# 2020-09-27_06-15-33.net
KiCad netlist of a schematic drawn in EasyEDA
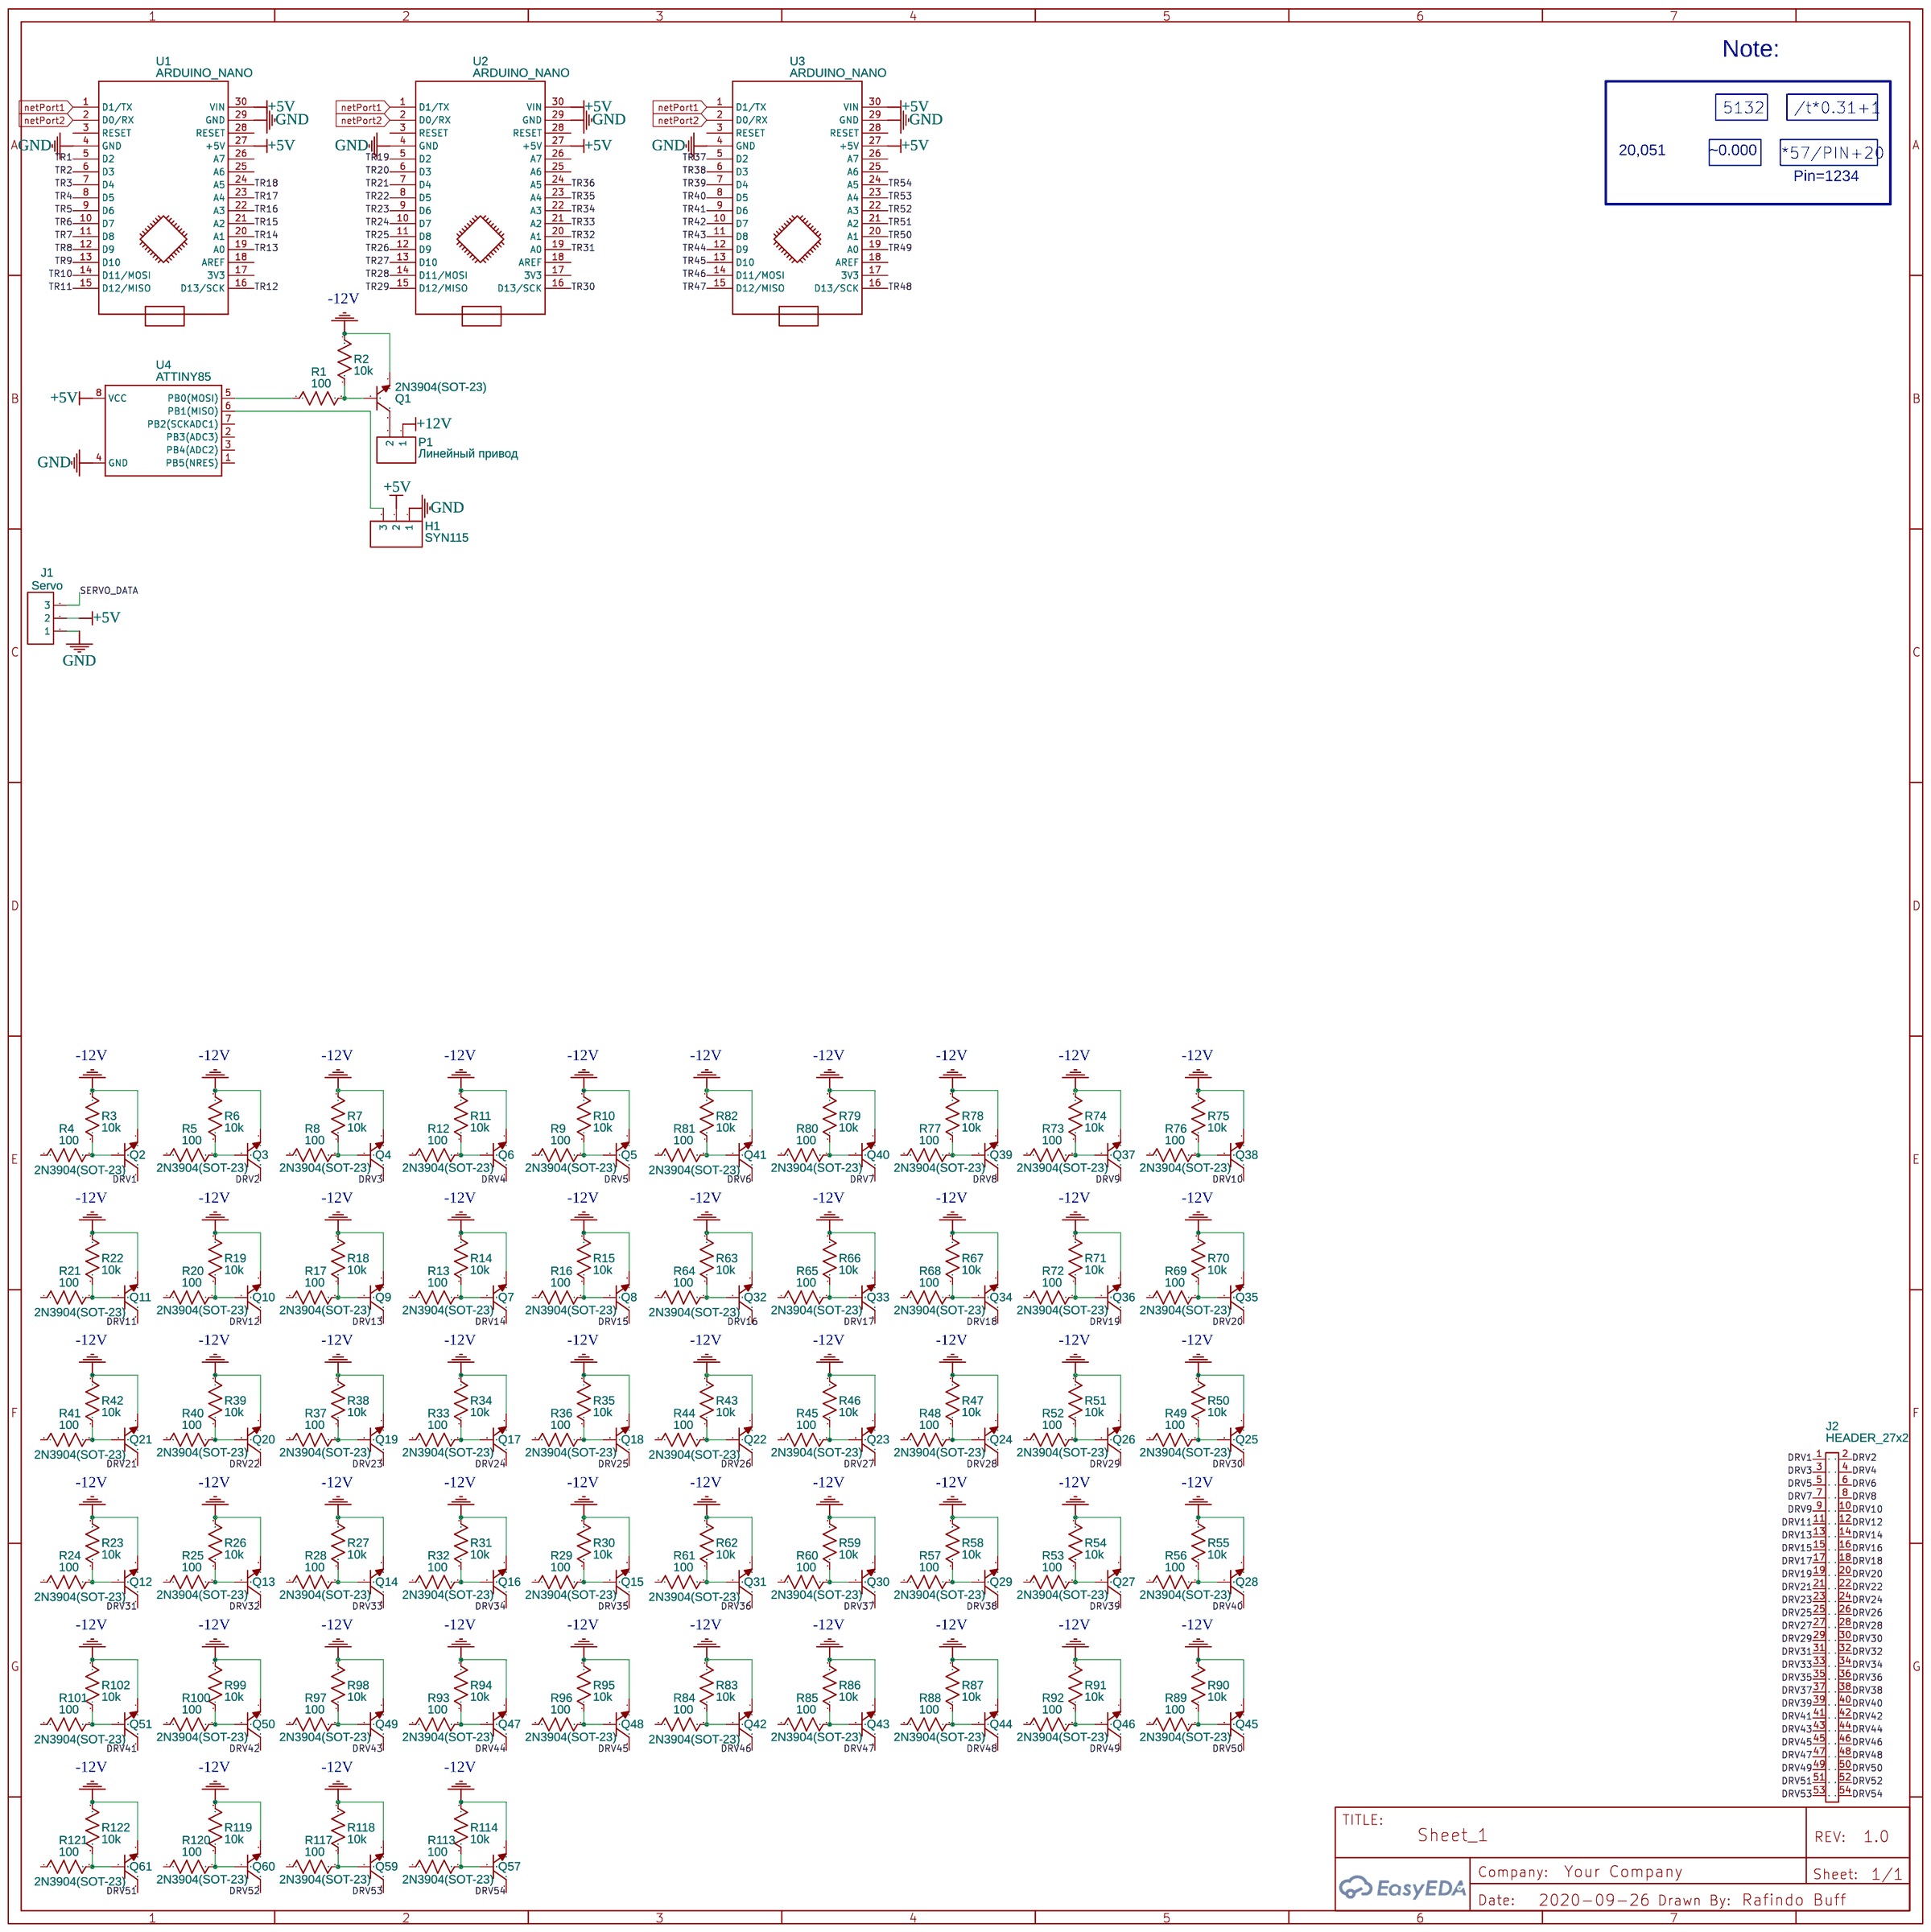
[diagram p0: schematic sheet]

(export (version "E")
  (design (tool "Eeschema 10.0.6"))
  (components
    (comp (ref "H1")
      (value "SYN115")
      (fields (field (name "BOM_Supplier Part") "C146690"))
      (libsource (lib "") (part "HDR-F-2.54_1x3"))
    )
    (comp (ref "J1")
      (value "Servo")
      (fields (field (name "BOM_Supplier Part") "C180248"))
      (libsource (lib "") (part "HDR-M-2.54_1x3"))
    )
    (comp (ref "J2") (value "HEADER_27x2") (libsource (lib "") (part "HEADER_27x2")))
    (comp (ref "P1") (value "Линейный привод") (libsource (lib "") (part "CONN-TH_2P-P5.00")))
    (comp (ref "Q1")
      (value "2N3904(SOT-23)")
      (fields
        (field (name "BOM_Manufacturer Part") "2n3904S-RTK/PS")
        (field (name "BOM_Supplier Part") "C18536")
      )
      (libsource (lib "") (part "2N3904(SOT-23)"))
    )
    (comp (ref "Q2")
      (value "2N3904(SOT-23)")
      (fields
        (field (name "BOM_Manufacturer Part") "2n3904S-RTK/PS")
        (field (name "BOM_Supplier Part") "C18536")
      )
      (libsource (lib "") (part "2N3904(SOT-23)"))
    )
    (comp (ref "Q3")
      (value "2N3904(SOT-23)")
      (fields
        (field (name "BOM_Manufacturer Part") "2n3904S-RTK/PS")
        (field (name "BOM_Supplier Part") "C18536")
      )
      (libsource (lib "") (part "2N3904(SOT-23)"))
    )
    (comp (ref "Q4")
      (value "2N3904(SOT-23)")
      (fields
        (field (name "BOM_Manufacturer Part") "2n3904S-RTK/PS")
        (field (name "BOM_Supplier Part") "C18536")
      )
      (libsource (lib "") (part "2N3904(SOT-23)"))
    )
    (comp (ref "Q5")
      (value "2N3904(SOT-23)")
      (fields
        (field (name "BOM_Manufacturer Part") "2n3904S-RTK/PS")
        (field (name "BOM_Supplier Part") "C18536")
      )
      (libsource (lib "") (part "2N3904(SOT-23)"))
    )
    (comp (ref "Q6")
      (value "2N3904(SOT-23)")
      (fields
        (field (name "BOM_Manufacturer Part") "2n3904S-RTK/PS")
        (field (name "BOM_Supplier Part") "C18536")
      )
      (libsource (lib "") (part "2N3904(SOT-23)"))
    )
    (comp (ref "Q7")
      (value "2N3904(SOT-23)")
      (fields
        (field (name "BOM_Manufacturer Part") "2n3904S-RTK/PS")
        (field (name "BOM_Supplier Part") "C18536")
      )
      (libsource (lib "") (part "2N3904(SOT-23)"))
    )
    (comp (ref "Q8")
      (value "2N3904(SOT-23)")
      (fields
        (field (name "BOM_Manufacturer Part") "2n3904S-RTK/PS")
        (field (name "BOM_Supplier Part") "C18536")
      )
      (libsource (lib "") (part "2N3904(SOT-23)"))
    )
    (comp (ref "Q9")
      (value "2N3904(SOT-23)")
      (fields
        (field (name "BOM_Manufacturer Part") "2n3904S-RTK/PS")
        (field (name "BOM_Supplier Part") "C18536")
      )
      (libsource (lib "") (part "2N3904(SOT-23)"))
    )
    (comp (ref "Q10")
      (value "2N3904(SOT-23)")
      (fields
        (field (name "BOM_Manufacturer Part") "2n3904S-RTK/PS")
        (field (name "BOM_Supplier Part") "C18536")
      )
      (libsource (lib "") (part "2N3904(SOT-23)"))
    )
    (comp (ref "Q11")
      (value "2N3904(SOT-23)")
      (fields
        (field (name "BOM_Manufacturer Part") "2n3904S-RTK/PS")
        (field (name "BOM_Supplier Part") "C18536")
      )
      (libsource (lib "") (part "2N3904(SOT-23)"))
    )
    (comp (ref "Q12")
      (value "2N3904(SOT-23)")
      (fields
        (field (name "BOM_Manufacturer Part") "2n3904S-RTK/PS")
        (field (name "BOM_Supplier Part") "C18536")
      )
      (libsource (lib "") (part "2N3904(SOT-23)"))
    )
    (comp (ref "Q13")
      (value "2N3904(SOT-23)")
      (fields
        (field (name "BOM_Manufacturer Part") "2n3904S-RTK/PS")
        (field (name "BOM_Supplier Part") "C18536")
      )
      (libsource (lib "") (part "2N3904(SOT-23)"))
    )
    (comp (ref "Q14")
      (value "2N3904(SOT-23)")
      (fields
        (field (name "BOM_Manufacturer Part") "2n3904S-RTK/PS")
        (field (name "BOM_Supplier Part") "C18536")
      )
      (libsource (lib "") (part "2N3904(SOT-23)"))
    )
    (comp (ref "Q15")
      (value "2N3904(SOT-23)")
      (fields
        (field (name "BOM_Manufacturer Part") "2n3904S-RTK/PS")
        (field (name "BOM_Supplier Part") "C18536")
      )
      (libsource (lib "") (part "2N3904(SOT-23)"))
    )
    (comp (ref "Q16")
      (value "2N3904(SOT-23)")
      (fields
        (field (name "BOM_Manufacturer Part") "2n3904S-RTK/PS")
        (field (name "BOM_Supplier Part") "C18536")
      )
      (libsource (lib "") (part "2N3904(SOT-23)"))
    )
    (comp (ref "Q17")
      (value "2N3904(SOT-23)")
      (fields
        (field (name "BOM_Manufacturer Part") "2n3904S-RTK/PS")
        (field (name "BOM_Supplier Part") "C18536")
      )
      (libsource (lib "") (part "2N3904(SOT-23)"))
    )
    (comp (ref "Q18")
      (value "2N3904(SOT-23)")
      (fields
        (field (name "BOM_Manufacturer Part") "2n3904S-RTK/PS")
        (field (name "BOM_Supplier Part") "C18536")
      )
      (libsource (lib "") (part "2N3904(SOT-23)"))
    )
    (comp (ref "Q19")
      (value "2N3904(SOT-23)")
      (fields
        (field (name "BOM_Manufacturer Part") "2n3904S-RTK/PS")
        (field (name "BOM_Supplier Part") "C18536")
      )
      (libsource (lib "") (part "2N3904(SOT-23)"))
    )
    (comp (ref "Q20")
      (value "2N3904(SOT-23)")
      (fields
        (field (name "BOM_Manufacturer Part") "2n3904S-RTK/PS")
        (field (name "BOM_Supplier Part") "C18536")
      )
      (libsource (lib "") (part "2N3904(SOT-23)"))
    )
    (comp (ref "Q21")
      (value "2N3904(SOT-23)")
      (fields
        (field (name "BOM_Manufacturer Part") "2n3904S-RTK/PS")
        (field (name "BOM_Supplier Part") "C18536")
      )
      (libsource (lib "") (part "2N3904(SOT-23)"))
    )
    (comp (ref "Q22")
      (value "2N3904(SOT-23)")
      (fields
        (field (name "BOM_Manufacturer Part") "2n3904S-RTK/PS")
        (field (name "BOM_Supplier Part") "C18536")
      )
      (libsource (lib "") (part "2N3904(SOT-23)"))
    )
    (comp (ref "Q23")
      (value "2N3904(SOT-23)")
      (fields
        (field (name "BOM_Manufacturer Part") "2n3904S-RTK/PS")
        (field (name "BOM_Supplier Part") "C18536")
      )
      (libsource (lib "") (part "2N3904(SOT-23)"))
    )
    (comp (ref "Q24")
      (value "2N3904(SOT-23)")
      (fields
        (field (name "BOM_Manufacturer Part") "2n3904S-RTK/PS")
        (field (name "BOM_Supplier Part") "C18536")
      )
      (libsource (lib "") (part "2N3904(SOT-23)"))
    )
    (comp (ref "Q25")
      (value "2N3904(SOT-23)")
      (fields
        (field (name "BOM_Manufacturer Part") "2n3904S-RTK/PS")
        (field (name "BOM_Supplier Part") "C18536")
      )
      (libsource (lib "") (part "2N3904(SOT-23)"))
    )
    (comp (ref "Q26")
      (value "2N3904(SOT-23)")
      (fields
        (field (name "BOM_Manufacturer Part") "2n3904S-RTK/PS")
        (field (name "BOM_Supplier Part") "C18536")
      )
      (libsource (lib "") (part "2N3904(SOT-23)"))
    )
    (comp (ref "Q27")
      (value "2N3904(SOT-23)")
      (fields
        (field (name "BOM_Manufacturer Part") "2n3904S-RTK/PS")
        (field (name "BOM_Supplier Part") "C18536")
      )
      (libsource (lib "") (part "2N3904(SOT-23)"))
    )
    (comp (ref "Q28")
      (value "2N3904(SOT-23)")
      (fields
        (field (name "BOM_Manufacturer Part") "2n3904S-RTK/PS")
        (field (name "BOM_Supplier Part") "C18536")
      )
      (libsource (lib "") (part "2N3904(SOT-23)"))
    )
    (comp (ref "Q29")
      (value "2N3904(SOT-23)")
      (fields
        (field (name "BOM_Manufacturer Part") "2n3904S-RTK/PS")
        (field (name "BOM_Supplier Part") "C18536")
      )
      (libsource (lib "") (part "2N3904(SOT-23)"))
    )
    (comp (ref "Q30")
      (value "2N3904(SOT-23)")
      (fields
        (field (name "BOM_Manufacturer Part") "2n3904S-RTK/PS")
        (field (name "BOM_Supplier Part") "C18536")
      )
      (libsource (lib "") (part "2N3904(SOT-23)"))
    )
    (comp (ref "Q31")
      (value "2N3904(SOT-23)")
      (fields
        (field (name "BOM_Manufacturer Part") "2n3904S-RTK/PS")
        (field (name "BOM_Supplier Part") "C18536")
      )
      (libsource (lib "") (part "2N3904(SOT-23)"))
    )
    (comp (ref "Q32")
      (value "2N3904(SOT-23)")
      (fields
        (field (name "BOM_Manufacturer Part") "2n3904S-RTK/PS")
        (field (name "BOM_Supplier Part") "C18536")
      )
      (libsource (lib "") (part "2N3904(SOT-23)"))
    )
    (comp (ref "Q33")
      (value "2N3904(SOT-23)")
      (fields
        (field (name "BOM_Manufacturer Part") "2n3904S-RTK/PS")
        (field (name "BOM_Supplier Part") "C18536")
      )
      (libsource (lib "") (part "2N3904(SOT-23)"))
    )
    (comp (ref "Q34")
      (value "2N3904(SOT-23)")
      (fields
        (field (name "BOM_Manufacturer Part") "2n3904S-RTK/PS")
        (field (name "BOM_Supplier Part") "C18536")
      )
      (libsource (lib "") (part "2N3904(SOT-23)"))
    )
    (comp (ref "Q35")
      (value "2N3904(SOT-23)")
      (fields
        (field (name "BOM_Manufacturer Part") "2n3904S-RTK/PS")
        (field (name "BOM_Supplier Part") "C18536")
      )
      (libsource (lib "") (part "2N3904(SOT-23)"))
    )
    (comp (ref "Q36")
      (value "2N3904(SOT-23)")
      (fields
        (field (name "BOM_Manufacturer Part") "2n3904S-RTK/PS")
        (field (name "BOM_Supplier Part") "C18536")
      )
      (libsource (lib "") (part "2N3904(SOT-23)"))
    )
    (comp (ref "Q37")
      (value "2N3904(SOT-23)")
      (fields
        (field (name "BOM_Manufacturer Part") "2n3904S-RTK/PS")
        (field (name "BOM_Supplier Part") "C18536")
      )
      (libsource (lib "") (part "2N3904(SOT-23)"))
    )
    (comp (ref "Q38")
      (value "2N3904(SOT-23)")
      (fields
        (field (name "BOM_Manufacturer Part") "2n3904S-RTK/PS")
        (field (name "BOM_Supplier Part") "C18536")
      )
      (libsource (lib "") (part "2N3904(SOT-23)"))
    )
    (comp (ref "Q39")
      (value "2N3904(SOT-23)")
      (fields
        (field (name "BOM_Manufacturer Part") "2n3904S-RTK/PS")
        (field (name "BOM_Supplier Part") "C18536")
      )
      (libsource (lib "") (part "2N3904(SOT-23)"))
    )
    (comp (ref "Q40")
      (value "2N3904(SOT-23)")
      (fields
        (field (name "BOM_Manufacturer Part") "2n3904S-RTK/PS")
        (field (name "BOM_Supplier Part") "C18536")
      )
      (libsource (lib "") (part "2N3904(SOT-23)"))
    )
    (comp (ref "Q41")
      (value "2N3904(SOT-23)")
      (fields
        (field (name "BOM_Manufacturer Part") "2n3904S-RTK/PS")
        (field (name "BOM_Supplier Part") "C18536")
      )
      (libsource (lib "") (part "2N3904(SOT-23)"))
    )
    (comp (ref "Q42")
      (value "2N3904(SOT-23)")
      (fields
        (field (name "BOM_Manufacturer Part") "2n3904S-RTK/PS")
        (field (name "BOM_Supplier Part") "C18536")
      )
      (libsource (lib "") (part "2N3904(SOT-23)"))
    )
    (comp (ref "Q43")
      (value "2N3904(SOT-23)")
      (fields
        (field (name "BOM_Manufacturer Part") "2n3904S-RTK/PS")
        (field (name "BOM_Supplier Part") "C18536")
      )
      (libsource (lib "") (part "2N3904(SOT-23)"))
    )
    (comp (ref "Q44")
      (value "2N3904(SOT-23)")
      (fields
        (field (name "BOM_Manufacturer Part") "2n3904S-RTK/PS")
        (field (name "BOM_Supplier Part") "C18536")
      )
      (libsource (lib "") (part "2N3904(SOT-23)"))
    )
    (comp (ref "Q45")
      (value "2N3904(SOT-23)")
      (fields
        (field (name "BOM_Manufacturer Part") "2n3904S-RTK/PS")
        (field (name "BOM_Supplier Part") "C18536")
      )
      (libsource (lib "") (part "2N3904(SOT-23)"))
    )
    (comp (ref "Q46")
      (value "2N3904(SOT-23)")
      (fields
        (field (name "BOM_Manufacturer Part") "2n3904S-RTK/PS")
        (field (name "BOM_Supplier Part") "C18536")
      )
      (libsource (lib "") (part "2N3904(SOT-23)"))
    )
    (comp (ref "Q47")
      (value "2N3904(SOT-23)")
      (fields
        (field (name "BOM_Manufacturer Part") "2n3904S-RTK/PS")
        (field (name "BOM_Supplier Part") "C18536")
      )
      (libsource (lib "") (part "2N3904(SOT-23)"))
    )
    (comp (ref "Q48")
      (value "2N3904(SOT-23)")
      (fields
        (field (name "BOM_Manufacturer Part") "2n3904S-RTK/PS")
        (field (name "BOM_Supplier Part") "C18536")
      )
      (libsource (lib "") (part "2N3904(SOT-23)"))
    )
    (comp (ref "Q49")
      (value "2N3904(SOT-23)")
      (fields
        (field (name "BOM_Manufacturer Part") "2n3904S-RTK/PS")
        (field (name "BOM_Supplier Part") "C18536")
      )
      (libsource (lib "") (part "2N3904(SOT-23)"))
    )
    (comp (ref "Q50")
      (value "2N3904(SOT-23)")
      (fields
        (field (name "BOM_Manufacturer Part") "2n3904S-RTK/PS")
        (field (name "BOM_Supplier Part") "C18536")
      )
      (libsource (lib "") (part "2N3904(SOT-23)"))
    )
    (comp (ref "Q51")
      (value "2N3904(SOT-23)")
      (fields
        (field (name "BOM_Manufacturer Part") "2n3904S-RTK/PS")
        (field (name "BOM_Supplier Part") "C18536")
      )
      (libsource (lib "") (part "2N3904(SOT-23)"))
    )
    (comp (ref "Q57")
      (value "2N3904(SOT-23)")
      (fields
        (field (name "BOM_Manufacturer Part") "2n3904S-RTK/PS")
        (field (name "BOM_Supplier Part") "C18536")
      )
      (libsource (lib "") (part "2N3904(SOT-23)"))
    )
    (comp (ref "Q59")
      (value "2N3904(SOT-23)")
      (fields
        (field (name "BOM_Manufacturer Part") "2n3904S-RTK/PS")
        (field (name "BOM_Supplier Part") "C18536")
      )
      (libsource (lib "") (part "2N3904(SOT-23)"))
    )
    (comp (ref "Q60")
      (value "2N3904(SOT-23)")
      (fields
        (field (name "BOM_Manufacturer Part") "2n3904S-RTK/PS")
        (field (name "BOM_Supplier Part") "C18536")
      )
      (libsource (lib "") (part "2N3904(SOT-23)"))
    )
    (comp (ref "Q61")
      (value "2N3904(SOT-23)")
      (fields
        (field (name "BOM_Manufacturer Part") "2n3904S-RTK/PS")
        (field (name "BOM_Supplier Part") "C18536")
      )
      (libsource (lib "") (part "2N3904(SOT-23)"))
    )
    (comp (ref "R1") (value "100") (libsource (lib "") (part "R_0603_US")))
    (comp (ref "R2") (value "10k") (libsource (lib "") (part "R_0603_US_1")))
    (comp (ref "R3") (value "10k") (libsource (lib "") (part "R_0603_US_1")))
    (comp (ref "R4") (value "100") (libsource (lib "") (part "R_0603_US")))
    (comp (ref "R5") (value "100") (libsource (lib "") (part "R_0603_US")))
    (comp (ref "R6") (value "10k") (libsource (lib "") (part "R_0603_US_1")))
    (comp (ref "R7") (value "10k") (libsource (lib "") (part "R_0603_US_1")))
    (comp (ref "R8") (value "100") (libsource (lib "") (part "R_0603_US")))
    (comp (ref "R9") (value "100") (libsource (lib "") (part "R_0603_US")))
    (comp (ref "R10") (value "10k") (libsource (lib "") (part "R_0603_US_1")))
    (comp (ref "R11") (value "10k") (libsource (lib "") (part "R_0603_US_1")))
    (comp (ref "R12") (value "100") (libsource (lib "") (part "R_0603_US")))
    (comp (ref "R13") (value "100") (libsource (lib "") (part "R_0603_US")))
    (comp (ref "R14") (value "10k") (libsource (lib "") (part "R_0603_US_1")))
    (comp (ref "R15") (value "10k") (libsource (lib "") (part "R_0603_US_1")))
    (comp (ref "R16") (value "100") (libsource (lib "") (part "R_0603_US")))
    (comp (ref "R17") (value "100") (libsource (lib "") (part "R_0603_US")))
    (comp (ref "R18") (value "10k") (libsource (lib "") (part "R_0603_US_1")))
    (comp (ref "R19") (value "10k") (libsource (lib "") (part "R_0603_US_1")))
    (comp (ref "R20") (value "100") (libsource (lib "") (part "R_0603_US")))
    (comp (ref "R21") (value "100") (libsource (lib "") (part "R_0603_US")))
    (comp (ref "R22") (value "10k") (libsource (lib "") (part "R_0603_US_1")))
    (comp (ref "R23") (value "10k") (libsource (lib "") (part "R_0603_US_1")))
    (comp (ref "R24") (value "100") (libsource (lib "") (part "R_0603_US")))
    (comp (ref "R25") (value "100") (libsource (lib "") (part "R_0603_US")))
    (comp (ref "R26") (value "10k") (libsource (lib "") (part "R_0603_US_1")))
    (comp (ref "R27") (value "10k") (libsource (lib "") (part "R_0603_US_1")))
    (comp (ref "R28") (value "100") (libsource (lib "") (part "R_0603_US")))
    (comp (ref "R29") (value "100") (libsource (lib "") (part "R_0603_US")))
    (comp (ref "R30") (value "10k") (libsource (lib "") (part "R_0603_US_1")))
    (comp (ref "R31") (value "10k") (libsource (lib "") (part "R_0603_US_1")))
    (comp (ref "R32") (value "100") (libsource (lib "") (part "R_0603_US")))
    (comp (ref "R33") (value "100") (libsource (lib "") (part "R_0603_US")))
    (comp (ref "R34") (value "10k") (libsource (lib "") (part "R_0603_US_1")))
    (comp (ref "R35") (value "10k") (libsource (lib "") (part "R_0603_US_1")))
    (comp (ref "R36") (value "100") (libsource (lib "") (part "R_0603_US")))
    (comp (ref "R37") (value "100") (libsource (lib "") (part "R_0603_US")))
    (comp (ref "R38") (value "10k") (libsource (lib "") (part "R_0603_US_1")))
    (comp (ref "R39") (value "10k") (libsource (lib "") (part "R_0603_US_1")))
    (comp (ref "R40") (value "100") (libsource (lib "") (part "R_0603_US")))
    (comp (ref "R41") (value "100") (libsource (lib "") (part "R_0603_US")))
    (comp (ref "R42") (value "10k") (libsource (lib "") (part "R_0603_US_1")))
    (comp (ref "R43") (value "10k") (libsource (lib "") (part "R_0603_US_1")))
    (comp (ref "R44") (value "100") (libsource (lib "") (part "R_0603_US")))
    (comp (ref "R45") (value "100") (libsource (lib "") (part "R_0603_US")))
    (comp (ref "R46") (value "10k") (libsource (lib "") (part "R_0603_US_1")))
    (comp (ref "R47") (value "10k") (libsource (lib "") (part "R_0603_US_1")))
    (comp (ref "R48") (value "100") (libsource (lib "") (part "R_0603_US")))
    (comp (ref "R49") (value "100") (libsource (lib "") (part "R_0603_US")))
    (comp (ref "R50") (value "10k") (libsource (lib "") (part "R_0603_US_1")))
    (comp (ref "R51") (value "10k") (libsource (lib "") (part "R_0603_US_1")))
    (comp (ref "R52") (value "100") (libsource (lib "") (part "R_0603_US")))
    (comp (ref "R53") (value "100") (libsource (lib "") (part "R_0603_US")))
    (comp (ref "R54") (value "10k") (libsource (lib "") (part "R_0603_US_1")))
    (comp (ref "R55") (value "10k") (libsource (lib "") (part "R_0603_US_1")))
    (comp (ref "R56") (value "100") (libsource (lib "") (part "R_0603_US")))
    (comp (ref "R57") (value "100") (libsource (lib "") (part "R_0603_US")))
    (comp (ref "R58") (value "10k") (libsource (lib "") (part "R_0603_US_1")))
    (comp (ref "R59") (value "10k") (libsource (lib "") (part "R_0603_US_1")))
    (comp (ref "R60") (value "100") (libsource (lib "") (part "R_0603_US")))
    (comp (ref "R61") (value "100") (libsource (lib "") (part "R_0603_US")))
    (comp (ref "R62") (value "10k") (libsource (lib "") (part "R_0603_US_1")))
    (comp (ref "R63") (value "10k") (libsource (lib "") (part "R_0603_US_1")))
    (comp (ref "R64") (value "100") (libsource (lib "") (part "R_0603_US")))
    (comp (ref "R65") (value "100") (libsource (lib "") (part "R_0603_US")))
    (comp (ref "R66") (value "10k") (libsource (lib "") (part "R_0603_US_1")))
    (comp (ref "R67") (value "10k") (libsource (lib "") (part "R_0603_US_1")))
    (comp (ref "R68") (value "100") (libsource (lib "") (part "R_0603_US")))
    (comp (ref "R69") (value "100") (libsource (lib "") (part "R_0603_US")))
    (comp (ref "R70") (value "10k") (libsource (lib "") (part "R_0603_US_1")))
    (comp (ref "R71") (value "10k") (libsource (lib "") (part "R_0603_US_1")))
    (comp (ref "R72") (value "100") (libsource (lib "") (part "R_0603_US")))
    (comp (ref "R73") (value "100") (libsource (lib "") (part "R_0603_US")))
    (comp (ref "R74") (value "10k") (libsource (lib "") (part "R_0603_US_1")))
    (comp (ref "R75") (value "10k") (libsource (lib "") (part "R_0603_US_1")))
    (comp (ref "R76") (value "100") (libsource (lib "") (part "R_0603_US")))
    (comp (ref "R77") (value "100") (libsource (lib "") (part "R_0603_US")))
    (comp (ref "R78") (value "10k") (libsource (lib "") (part "R_0603_US_1")))
    (comp (ref "R79") (value "10k") (libsource (lib "") (part "R_0603_US_1")))
    (comp (ref "R80") (value "100") (libsource (lib "") (part "R_0603_US")))
    (comp (ref "R81") (value "100") (libsource (lib "") (part "R_0603_US")))
    (comp (ref "R82") (value "10k") (libsource (lib "") (part "R_0603_US_1")))
    (comp (ref "R83") (value "10k") (libsource (lib "") (part "R_0603_US_1")))
    (comp (ref "R84") (value "100") (libsource (lib "") (part "R_0603_US")))
    (comp (ref "R85") (value "100") (libsource (lib "") (part "R_0603_US")))
    (comp (ref "R86") (value "10k") (libsource (lib "") (part "R_0603_US_1")))
    (comp (ref "R87") (value "10k") (libsource (lib "") (part "R_0603_US_1")))
    (comp (ref "R88") (value "100") (libsource (lib "") (part "R_0603_US")))
    (comp (ref "R89") (value "100") (libsource (lib "") (part "R_0603_US")))
    (comp (ref "R90") (value "10k") (libsource (lib "") (part "R_0603_US_1")))
    (comp (ref "R91") (value "10k") (libsource (lib "") (part "R_0603_US_1")))
    (comp (ref "R92") (value "100") (libsource (lib "") (part "R_0603_US")))
    (comp (ref "R93") (value "100") (libsource (lib "") (part "R_0603_US")))
    (comp (ref "R94") (value "10k") (libsource (lib "") (part "R_0603_US_1")))
    (comp (ref "R95") (value "10k") (libsource (lib "") (part "R_0603_US_1")))
    (comp (ref "R96") (value "100") (libsource (lib "") (part "R_0603_US")))
    (comp (ref "R97") (value "100") (libsource (lib "") (part "R_0603_US")))
    (comp (ref "R98") (value "10k") (libsource (lib "") (part "R_0603_US_1")))
    (comp (ref "R99") (value "10k") (libsource (lib "") (part "R_0603_US_1")))
    (comp (ref "R100") (value "100") (libsource (lib "") (part "R_0603_US")))
    (comp (ref "R101") (value "100") (libsource (lib "") (part "R_0603_US")))
    (comp (ref "R102") (value "10k") (libsource (lib "") (part "R_0603_US_1")))
    (comp (ref "R113") (value "100") (libsource (lib "") (part "R_0603_US")))
    (comp (ref "R114") (value "10k") (libsource (lib "") (part "R_0603_US_1")))
    (comp (ref "R117") (value "100") (libsource (lib "") (part "R_0603_US")))
    (comp (ref "R118") (value "10k") (libsource (lib "") (part "R_0603_US_1")))
    (comp (ref "R119") (value "10k") (libsource (lib "") (part "R_0603_US_1")))
    (comp (ref "R120") (value "100") (libsource (lib "") (part "R_0603_US")))
    (comp (ref "R121") (value "100") (libsource (lib "") (part "R_0603_US")))
    (comp (ref "R122") (value "10k") (libsource (lib "") (part "R_0603_US_1")))
    (comp (ref "U1") (value "ARDUINO_NANO") (libsource (lib "") (part "ARDUINO_NANO")))
    (comp (ref "U2") (value "ARDUINO_NANO") (libsource (lib "") (part "ARDUINO_NANO")))
    (comp (ref "U3") (value "ARDUINO_NANO") (libsource (lib "") (part "ARDUINO_NANO")))
    (comp (ref "U4") (value "ATTINY85") (libsource (lib "") (part "ATTINY13")))
  )
  (nets
    (net (code "1") (name "+5V") (class "Default")
      (node (ref "H1") (pin "2") (pinfunction "2_2") (pintype "input"))
      (node (ref "J1") (pin "2") (pinfunction "2_2") (pintype "input"))
      (node (ref "U1") (pin "27") (pinfunction "+5V_27") (pintype "unspecified"))
      (node (ref "U1") (pin "30") (pinfunction "VIN_30") (pintype "unspecified"))
      (node (ref "U2") (pin "27") (pinfunction "+5V_27") (pintype "unspecified"))
      (node (ref "U2") (pin "30") (pinfunction "VIN_30") (pintype "unspecified"))
      (node (ref "U3") (pin "27") (pinfunction "+5V_27") (pintype "unspecified"))
      (node (ref "U3") (pin "30") (pinfunction "VIN_30") (pintype "unspecified"))
      (node (ref "U4") (pin "8") (pinfunction "VCC_8") (pintype "unspecified"))
    )
    (net (code "2") (name "+12V") (class "Default")
      (node (ref "P1") (pin "1") (pinfunction "1_1") (pintype "unspecified"))
    )
    (net (code "3") (name "-12V") (class "Default")
      (node (ref "Q1") (pin "1") (pinfunction "E_1") (pintype "input"))
      (node (ref "Q10") (pin "1") (pinfunction "E_1") (pintype "input"))
      (node (ref "Q11") (pin "1") (pinfunction "E_1") (pintype "input"))
      (node (ref "Q12") (pin "1") (pinfunction "E_1") (pintype "input"))
      (node (ref "Q13") (pin "1") (pinfunction "E_1") (pintype "input"))
      (node (ref "Q14") (pin "1") (pinfunction "E_1") (pintype "input"))
      (node (ref "Q15") (pin "1") (pinfunction "E_1") (pintype "input"))
      (node (ref "Q16") (pin "1") (pinfunction "E_1") (pintype "input"))
      (node (ref "Q17") (pin "1") (pinfunction "E_1") (pintype "input"))
      (node (ref "Q18") (pin "1") (pinfunction "E_1") (pintype "input"))
      (node (ref "Q19") (pin "1") (pinfunction "E_1") (pintype "input"))
      (node (ref "Q2") (pin "1") (pinfunction "E_1") (pintype "input"))
      (node (ref "Q20") (pin "1") (pinfunction "E_1") (pintype "input"))
      (node (ref "Q21") (pin "1") (pinfunction "E_1") (pintype "input"))
      (node (ref "Q22") (pin "1") (pinfunction "E_1") (pintype "input"))
      (node (ref "Q23") (pin "1") (pinfunction "E_1") (pintype "input"))
      (node (ref "Q24") (pin "1") (pinfunction "E_1") (pintype "input"))
      (node (ref "Q25") (pin "1") (pinfunction "E_1") (pintype "input"))
      (node (ref "Q26") (pin "1") (pinfunction "E_1") (pintype "input"))
      (node (ref "Q27") (pin "1") (pinfunction "E_1") (pintype "input"))
      (node (ref "Q28") (pin "1") (pinfunction "E_1") (pintype "input"))
      (node (ref "Q29") (pin "1") (pinfunction "E_1") (pintype "input"))
      (node (ref "Q3") (pin "1") (pinfunction "E_1") (pintype "input"))
      (node (ref "Q30") (pin "1") (pinfunction "E_1") (pintype "input"))
      (node (ref "Q31") (pin "1") (pinfunction "E_1") (pintype "input"))
      (node (ref "Q32") (pin "1") (pinfunction "E_1") (pintype "input"))
      (node (ref "Q33") (pin "1") (pinfunction "E_1") (pintype "input"))
      (node (ref "Q34") (pin "1") (pinfunction "E_1") (pintype "input"))
      (node (ref "Q35") (pin "1") (pinfunction "E_1") (pintype "input"))
      (node (ref "Q36") (pin "1") (pinfunction "E_1") (pintype "input"))
      (node (ref "Q37") (pin "1") (pinfunction "E_1") (pintype "input"))
      (node (ref "Q38") (pin "1") (pinfunction "E_1") (pintype "input"))
      (node (ref "Q39") (pin "1") (pinfunction "E_1") (pintype "input"))
      (node (ref "Q4") (pin "1") (pinfunction "E_1") (pintype "input"))
      (node (ref "Q40") (pin "1") (pinfunction "E_1") (pintype "input"))
      (node (ref "Q41") (pin "1") (pinfunction "E_1") (pintype "input"))
      (node (ref "Q42") (pin "1") (pinfunction "E_1") (pintype "input"))
      (node (ref "Q43") (pin "1") (pinfunction "E_1") (pintype "input"))
      (node (ref "Q44") (pin "1") (pinfunction "E_1") (pintype "input"))
      (node (ref "Q45") (pin "1") (pinfunction "E_1") (pintype "input"))
      (node (ref "Q46") (pin "1") (pinfunction "E_1") (pintype "input"))
      (node (ref "Q47") (pin "1") (pinfunction "E_1") (pintype "input"))
      (node (ref "Q48") (pin "1") (pinfunction "E_1") (pintype "input"))
      (node (ref "Q49") (pin "1") (pinfunction "E_1") (pintype "input"))
      (node (ref "Q5") (pin "1") (pinfunction "E_1") (pintype "input"))
      (node (ref "Q50") (pin "1") (pinfunction "E_1") (pintype "input"))
      (node (ref "Q51") (pin "1") (pinfunction "E_1") (pintype "input"))
      (node (ref "Q57") (pin "1") (pinfunction "E_1") (pintype "input"))
      (node (ref "Q59") (pin "1") (pinfunction "E_1") (pintype "input"))
      (node (ref "Q6") (pin "1") (pinfunction "E_1") (pintype "input"))
      (node (ref "Q60") (pin "1") (pinfunction "E_1") (pintype "input"))
      (node (ref "Q61") (pin "1") (pinfunction "E_1") (pintype "input"))
      (node (ref "Q7") (pin "1") (pinfunction "E_1") (pintype "input"))
      (node (ref "Q8") (pin "1") (pinfunction "E_1") (pintype "input"))
      (node (ref "Q9") (pin "1") (pinfunction "E_1") (pintype "input"))
      (node (ref "R10") (pin "2") (pinfunction "2_2") (pintype "unspecified"))
      (node (ref "R102") (pin "2") (pinfunction "2_2") (pintype "unspecified"))
      (node (ref "R11") (pin "2") (pinfunction "2_2") (pintype "unspecified"))
      (node (ref "R114") (pin "2") (pinfunction "2_2") (pintype "unspecified"))
      (node (ref "R118") (pin "2") (pinfunction "2_2") (pintype "unspecified"))
      (node (ref "R119") (pin "2") (pinfunction "2_2") (pintype "unspecified"))
      (node (ref "R122") (pin "2") (pinfunction "2_2") (pintype "unspecified"))
      (node (ref "R14") (pin "2") (pinfunction "2_2") (pintype "unspecified"))
      (node (ref "R15") (pin "2") (pinfunction "2_2") (pintype "unspecified"))
      (node (ref "R18") (pin "2") (pinfunction "2_2") (pintype "unspecified"))
      (node (ref "R19") (pin "2") (pinfunction "2_2") (pintype "unspecified"))
      (node (ref "R2") (pin "2") (pinfunction "2_2") (pintype "unspecified"))
      (node (ref "R22") (pin "2") (pinfunction "2_2") (pintype "unspecified"))
      (node (ref "R23") (pin "2") (pinfunction "2_2") (pintype "unspecified"))
      (node (ref "R26") (pin "2") (pinfunction "2_2") (pintype "unspecified"))
      (node (ref "R27") (pin "2") (pinfunction "2_2") (pintype "unspecified"))
      (node (ref "R3") (pin "2") (pinfunction "2_2") (pintype "unspecified"))
      (node (ref "R30") (pin "2") (pinfunction "2_2") (pintype "unspecified"))
      (node (ref "R31") (pin "2") (pinfunction "2_2") (pintype "unspecified"))
      (node (ref "R34") (pin "2") (pinfunction "2_2") (pintype "unspecified"))
      (node (ref "R35") (pin "2") (pinfunction "2_2") (pintype "unspecified"))
      (node (ref "R38") (pin "2") (pinfunction "2_2") (pintype "unspecified"))
      (node (ref "R39") (pin "2") (pinfunction "2_2") (pintype "unspecified"))
      (node (ref "R42") (pin "2") (pinfunction "2_2") (pintype "unspecified"))
      (node (ref "R43") (pin "2") (pinfunction "2_2") (pintype "unspecified"))
      (node (ref "R46") (pin "2") (pinfunction "2_2") (pintype "unspecified"))
      (node (ref "R47") (pin "2") (pinfunction "2_2") (pintype "unspecified"))
      (node (ref "R50") (pin "2") (pinfunction "2_2") (pintype "unspecified"))
      (node (ref "R51") (pin "2") (pinfunction "2_2") (pintype "unspecified"))
      (node (ref "R54") (pin "2") (pinfunction "2_2") (pintype "unspecified"))
      (node (ref "R55") (pin "2") (pinfunction "2_2") (pintype "unspecified"))
      (node (ref "R58") (pin "2") (pinfunction "2_2") (pintype "unspecified"))
      (node (ref "R59") (pin "2") (pinfunction "2_2") (pintype "unspecified"))
      (node (ref "R6") (pin "2") (pinfunction "2_2") (pintype "unspecified"))
      (node (ref "R62") (pin "2") (pinfunction "2_2") (pintype "unspecified"))
      (node (ref "R63") (pin "2") (pinfunction "2_2") (pintype "unspecified"))
      (node (ref "R66") (pin "2") (pinfunction "2_2") (pintype "unspecified"))
      (node (ref "R67") (pin "2") (pinfunction "2_2") (pintype "unspecified"))
      (node (ref "R7") (pin "2") (pinfunction "2_2") (pintype "unspecified"))
      (node (ref "R70") (pin "2") (pinfunction "2_2") (pintype "unspecified"))
      (node (ref "R71") (pin "2") (pinfunction "2_2") (pintype "unspecified"))
      (node (ref "R74") (pin "2") (pinfunction "2_2") (pintype "unspecified"))
      (node (ref "R75") (pin "2") (pinfunction "2_2") (pintype "unspecified"))
      (node (ref "R78") (pin "2") (pinfunction "2_2") (pintype "unspecified"))
      (node (ref "R79") (pin "2") (pinfunction "2_2") (pintype "unspecified"))
      (node (ref "R82") (pin "2") (pinfunction "2_2") (pintype "unspecified"))
      (node (ref "R83") (pin "2") (pinfunction "2_2") (pintype "unspecified"))
      (node (ref "R86") (pin "2") (pinfunction "2_2") (pintype "unspecified"))
      (node (ref "R87") (pin "2") (pinfunction "2_2") (pintype "unspecified"))
      (node (ref "R90") (pin "2") (pinfunction "2_2") (pintype "unspecified"))
      (node (ref "R91") (pin "2") (pinfunction "2_2") (pintype "unspecified"))
      (node (ref "R94") (pin "2") (pinfunction "2_2") (pintype "unspecified"))
      (node (ref "R95") (pin "2") (pinfunction "2_2") (pintype "unspecified"))
      (node (ref "R98") (pin "2") (pinfunction "2_2") (pintype "unspecified"))
      (node (ref "R99") (pin "2") (pinfunction "2_2") (pintype "unspecified"))
    )
    (net (code "4") (name "/DRV1") (class "Default")
      (node (ref "J2") (pin "1") (pinfunction "1_1") (pintype "unspecified"))
      (node (ref "Q2") (pin "3") (pinfunction "C_3") (pintype "input"))
    )
    (net (code "5") (name "/DRV2") (class "Default")
      (node (ref "J2") (pin "2") (pinfunction "2_2") (pintype "unspecified"))
      (node (ref "Q3") (pin "3") (pinfunction "C_3") (pintype "input"))
    )
    (net (code "6") (name "/DRV3") (class "Default")
      (node (ref "J2") (pin "3") (pinfunction "3_3") (pintype "unspecified"))
      (node (ref "Q4") (pin "3") (pinfunction "C_3") (pintype "input"))
    )
    (net (code "7") (name "/DRV4") (class "Default")
      (node (ref "J2") (pin "4") (pinfunction "4_4") (pintype "unspecified"))
      (node (ref "Q6") (pin "3") (pinfunction "C_3") (pintype "input"))
    )
    (net (code "8") (name "/DRV5") (class "Default")
      (node (ref "J2") (pin "5") (pinfunction "5_5") (pintype "unspecified"))
      (node (ref "Q5") (pin "3") (pinfunction "C_3") (pintype "input"))
    )
    (net (code "9") (name "/DRV6") (class "Default")
      (node (ref "J2") (pin "6") (pinfunction "6_6") (pintype "unspecified"))
      (node (ref "Q41") (pin "3") (pinfunction "C_3") (pintype "input"))
    )
    (net (code "10") (name "/DRV7") (class "Default")
      (node (ref "J2") (pin "7") (pinfunction "7_7") (pintype "unspecified"))
      (node (ref "Q40") (pin "3") (pinfunction "C_3") (pintype "input"))
    )
    (net (code "11") (name "/DRV8") (class "Default")
      (node (ref "J2") (pin "8") (pinfunction "8_8") (pintype "unspecified"))
      (node (ref "Q39") (pin "3") (pinfunction "C_3") (pintype "input"))
    )
    (net (code "12") (name "/DRV9") (class "Default")
      (node (ref "J2") (pin "9") (pinfunction "9_9") (pintype "unspecified"))
      (node (ref "Q37") (pin "3") (pinfunction "C_3") (pintype "input"))
    )
    (net (code "13") (name "/DRV10") (class "Default")
      (node (ref "J2") (pin "10") (pinfunction "10_10") (pintype "unspecified"))
      (node (ref "Q38") (pin "3") (pinfunction "C_3") (pintype "input"))
    )
    (net (code "14") (name "/DRV11") (class "Default")
      (node (ref "J2") (pin "11") (pinfunction "11_11") (pintype "unspecified"))
      (node (ref "Q11") (pin "3") (pinfunction "C_3") (pintype "input"))
    )
    (net (code "15") (name "/DRV12") (class "Default")
      (node (ref "J2") (pin "12") (pinfunction "12_12") (pintype "unspecified"))
      (node (ref "Q10") (pin "3") (pinfunction "C_3") (pintype "input"))
    )
    (net (code "16") (name "/DRV13") (class "Default")
      (node (ref "J2") (pin "13") (pinfunction "13_13") (pintype "unspecified"))
      (node (ref "Q9") (pin "3") (pinfunction "C_3") (pintype "input"))
    )
    (net (code "17") (name "/DRV14") (class "Default")
      (node (ref "J2") (pin "14") (pinfunction "14_14") (pintype "unspecified"))
      (node (ref "Q7") (pin "3") (pinfunction "C_3") (pintype "input"))
    )
    (net (code "18") (name "/DRV15") (class "Default")
      (node (ref "J2") (pin "15") (pinfunction "15_15") (pintype "unspecified"))
      (node (ref "Q8") (pin "3") (pinfunction "C_3") (pintype "input"))
    )
    (net (code "19") (name "/DRV16") (class "Default")
      (node (ref "J2") (pin "16") (pinfunction "16_16") (pintype "unspecified"))
    )
    (net (code "20") (name "/DRV17") (class "Default")
      (node (ref "J2") (pin "17") (pinfunction "17_17") (pintype "unspecified"))
      (node (ref "Q33") (pin "3") (pinfunction "C_3") (pintype "input"))
    )
    (net (code "21") (name "/DRV18") (class "Default")
      (node (ref "J2") (pin "18") (pinfunction "18_18") (pintype "unspecified"))
      (node (ref "Q34") (pin "3") (pinfunction "C_3") (pintype "input"))
    )
    (net (code "22") (name "/DRV19") (class "Default")
      (node (ref "J2") (pin "19") (pinfunction "19_19") (pintype "unspecified"))
      (node (ref "Q36") (pin "3") (pinfunction "C_3") (pintype "input"))
    )
    (net (code "23") (name "/DRV20") (class "Default")
      (node (ref "J2") (pin "20") (pinfunction "20_20") (pintype "unspecified"))
      (node (ref "Q35") (pin "3") (pinfunction "C_3") (pintype "input"))
    )
    (net (code "24") (name "/DRV21") (class "Default")
      (node (ref "J2") (pin "21") (pinfunction "21_21") (pintype "unspecified"))
      (node (ref "Q21") (pin "3") (pinfunction "C_3") (pintype "input"))
    )
    (net (code "25") (name "/DRV22") (class "Default")
      (node (ref "J2") (pin "22") (pinfunction "22_22") (pintype "unspecified"))
      (node (ref "Q20") (pin "3") (pinfunction "C_3") (pintype "input"))
    )
    (net (code "26") (name "/DRV23") (class "Default")
      (node (ref "J2") (pin "23") (pinfunction "23_23") (pintype "unspecified"))
      (node (ref "Q19") (pin "3") (pinfunction "C_3") (pintype "input"))
    )
    (net (code "27") (name "/DRV24") (class "Default")
      (node (ref "J2") (pin "24") (pinfunction "24_24") (pintype "unspecified"))
      (node (ref "Q17") (pin "3") (pinfunction "C_3") (pintype "input"))
    )
    (net (code "28") (name "/DRV25") (class "Default")
      (node (ref "J2") (pin "25") (pinfunction "25_25") (pintype "unspecified"))
      (node (ref "Q18") (pin "3") (pinfunction "C_3") (pintype "input"))
    )
    (net (code "29") (name "/DRV26") (class "Default")
      (node (ref "J2") (pin "26") (pinfunction "26_26") (pintype "unspecified"))
      (node (ref "Q22") (pin "3") (pinfunction "C_3") (pintype "input"))
    )
    (net (code "30") (name "/DRV27") (class "Default")
      (node (ref "J2") (pin "27") (pinfunction "27_27") (pintype "unspecified"))
      (node (ref "Q23") (pin "3") (pinfunction "C_3") (pintype "input"))
    )
    (net (code "31") (name "/DRV28") (class "Default")
      (node (ref "J2") (pin "28") (pinfunction "28_28") (pintype "unspecified"))
      (node (ref "Q24") (pin "3") (pinfunction "C_3") (pintype "input"))
    )
    (net (code "32") (name "/DRV29") (class "Default")
      (node (ref "J2") (pin "29") (pinfunction "29_29") (pintype "unspecified"))
      (node (ref "Q26") (pin "3") (pinfunction "C_3") (pintype "input"))
    )
    (net (code "33") (name "/DRV30") (class "Default")
      (node (ref "J2") (pin "30") (pinfunction "30_30") (pintype "unspecified"))
      (node (ref "Q25") (pin "3") (pinfunction "C_3") (pintype "input"))
    )
    (net (code "34") (name "/DRV31") (class "Default")
      (node (ref "J2") (pin "31") (pinfunction "31_31") (pintype "unspecified"))
      (node (ref "Q12") (pin "3") (pinfunction "C_3") (pintype "input"))
    )
    (net (code "35") (name "/DRV32") (class "Default")
      (node (ref "J2") (pin "32") (pinfunction "32_32") (pintype "unspecified"))
      (node (ref "Q13") (pin "3") (pinfunction "C_3") (pintype "input"))
    )
    (net (code "36") (name "/DRV33") (class "Default")
      (node (ref "J2") (pin "33") (pinfunction "33_33") (pintype "unspecified"))
      (node (ref "Q14") (pin "3") (pinfunction "C_3") (pintype "input"))
    )
    (net (code "37") (name "/DRV34") (class "Default")
      (node (ref "J2") (pin "34") (pinfunction "34_34") (pintype "unspecified"))
      (node (ref "Q16") (pin "3") (pinfunction "C_3") (pintype "input"))
    )
    (net (code "38") (name "/DRV35") (class "Default")
      (node (ref "J2") (pin "35") (pinfunction "35_35") (pintype "unspecified"))
      (node (ref "Q15") (pin "3") (pinfunction "C_3") (pintype "input"))
    )
    (net (code "39") (name "/DRV36") (class "Default")
      (node (ref "J2") (pin "36") (pinfunction "36_36") (pintype "unspecified"))
      (node (ref "Q31") (pin "3") (pinfunction "C_3") (pintype "input"))
    )
    (net (code "40") (name "/DRV37") (class "Default")
      (node (ref "J2") (pin "37") (pinfunction "37_37") (pintype "unspecified"))
      (node (ref "Q30") (pin "3") (pinfunction "C_3") (pintype "input"))
    )
    (net (code "41") (name "/DRV38") (class "Default")
      (node (ref "J2") (pin "38") (pinfunction "38_38") (pintype "unspecified"))
      (node (ref "Q29") (pin "3") (pinfunction "C_3") (pintype "input"))
    )
    (net (code "42") (name "/DRV39") (class "Default")
      (node (ref "J2") (pin "39") (pinfunction "39_39") (pintype "unspecified"))
      (node (ref "Q27") (pin "3") (pinfunction "C_3") (pintype "input"))
    )
    (net (code "43") (name "/DRV40") (class "Default")
      (node (ref "J2") (pin "40") (pinfunction "40_40") (pintype "unspecified"))
      (node (ref "Q28") (pin "3") (pinfunction "C_3") (pintype "input"))
    )
    (net (code "44") (name "/DRV41") (class "Default")
      (node (ref "J2") (pin "41") (pinfunction "41_41") (pintype "unspecified"))
      (node (ref "Q51") (pin "3") (pinfunction "C_3") (pintype "input"))
    )
    (net (code "45") (name "/DRV42") (class "Default")
      (node (ref "J2") (pin "42") (pinfunction "42_42") (pintype "unspecified"))
      (node (ref "Q50") (pin "3") (pinfunction "C_3") (pintype "input"))
    )
    (net (code "46") (name "/DRV43") (class "Default")
      (node (ref "J2") (pin "43") (pinfunction "43_43") (pintype "unspecified"))
      (node (ref "Q49") (pin "3") (pinfunction "C_3") (pintype "input"))
    )
    (net (code "47") (name "/DRV44") (class "Default")
      (node (ref "J2") (pin "44") (pinfunction "44_44") (pintype "unspecified"))
      (node (ref "Q47") (pin "3") (pinfunction "C_3") (pintype "input"))
    )
    (net (code "48") (name "/DRV45") (class "Default")
      (node (ref "J2") (pin "45") (pinfunction "45_45") (pintype "unspecified"))
      (node (ref "Q48") (pin "3") (pinfunction "C_3") (pintype "input"))
    )
    (net (code "49") (name "/DRV46") (class "Default")
      (node (ref "J2") (pin "46") (pinfunction "46_46") (pintype "unspecified"))
      (node (ref "Q42") (pin "3") (pinfunction "C_3") (pintype "input"))
    )
    (net (code "50") (name "/DRV47") (class "Default")
      (node (ref "J2") (pin "47") (pinfunction "47_47") (pintype "unspecified"))
      (node (ref "Q43") (pin "3") (pinfunction "C_3") (pintype "input"))
    )
    (net (code "51") (name "/DRV48") (class "Default")
      (node (ref "J2") (pin "48") (pinfunction "48_48") (pintype "unspecified"))
      (node (ref "Q44") (pin "3") (pinfunction "C_3") (pintype "input"))
    )
    (net (code "52") (name "/DRV49") (class "Default")
      (node (ref "J2") (pin "49") (pinfunction "49_49") (pintype "unspecified"))
      (node (ref "Q46") (pin "3") (pinfunction "C_3") (pintype "input"))
    )
    (net (code "53") (name "/DRV50") (class "Default")
      (node (ref "J2") (pin "50") (pinfunction "50_50") (pintype "unspecified"))
      (node (ref "Q45") (pin "3") (pinfunction "C_3") (pintype "input"))
    )
    (net (code "54") (name "/DRV51") (class "Default")
      (node (ref "J2") (pin "51") (pinfunction "51_51") (pintype "unspecified"))
      (node (ref "Q61") (pin "3") (pinfunction "C_3") (pintype "input"))
    )
    (net (code "55") (name "/DRV52") (class "Default")
      (node (ref "J2") (pin "52") (pinfunction "52_52") (pintype "unspecified"))
      (node (ref "Q60") (pin "3") (pinfunction "C_3") (pintype "input"))
    )
    (net (code "56") (name "/DRV53") (class "Default")
      (node (ref "J2") (pin "53") (pinfunction "53_53") (pintype "unspecified"))
      (node (ref "Q59") (pin "3") (pinfunction "C_3") (pintype "input"))
    )
    (net (code "57") (name "/DRV54") (class "Default")
      (node (ref "J2") (pin "54") (pinfunction "54_54") (pintype "unspecified"))
      (node (ref "Q57") (pin "3") (pinfunction "C_3") (pintype "input"))
    )
    (net (code "58") (name "/SERVO_DATA") (class "Default")
      (node (ref "J1") (pin "3") (pinfunction "3_3") (pintype "input"))
    )
    (net (code "59") (name "/TR1") (class "Default")
      (node (ref "U1") (pin "5") (pinfunction "D2_5") (pintype "unspecified"))
    )
    (net (code "60") (name "/TR2") (class "Default")
      (node (ref "U1") (pin "6") (pinfunction "D3_6") (pintype "unspecified"))
    )
    (net (code "61") (name "/TR3") (class "Default")
      (node (ref "U1") (pin "7") (pinfunction "D4_7") (pintype "unspecified"))
    )
    (net (code "62") (name "/TR4") (class "Default")
      (node (ref "U1") (pin "8") (pinfunction "D5_8") (pintype "unspecified"))
    )
    (net (code "63") (name "/TR5") (class "Default")
      (node (ref "U1") (pin "9") (pinfunction "D6_9") (pintype "unspecified"))
    )
    (net (code "64") (name "/TR6") (class "Default")
      (node (ref "U1") (pin "10") (pinfunction "D7_10") (pintype "unspecified"))
    )
    (net (code "65") (name "/TR7") (class "Default")
      (node (ref "U1") (pin "11") (pinfunction "D8_11") (pintype "unspecified"))
    )
    (net (code "66") (name "/TR8") (class "Default")
      (node (ref "U1") (pin "12") (pinfunction "D9_12") (pintype "unspecified"))
    )
    (net (code "67") (name "/TR9") (class "Default")
      (node (ref "U1") (pin "13") (pinfunction "D10_13") (pintype "unspecified"))
    )
    (net (code "68") (name "/TR10") (class "Default")
      (node (ref "U1") (pin "14") (pinfunction "D11/MOSI_14") (pintype "unspecified"))
    )
    (net (code "69") (name "/TR11") (class "Default")
      (node (ref "U1") (pin "15") (pinfunction "D12/MISO_15") (pintype "unspecified"))
    )
    (net (code "70") (name "/TR12") (class "Default")
      (node (ref "U1") (pin "16") (pinfunction "D13/SCK_16") (pintype "unspecified"))
    )
    (net (code "71") (name "/TR13") (class "Default")
      (node (ref "U1") (pin "19") (pinfunction "A0_19") (pintype "unspecified"))
    )
    (net (code "72") (name "/TR14") (class "Default")
      (node (ref "U1") (pin "20") (pinfunction "A1_20") (pintype "unspecified"))
    )
    (net (code "73") (name "/TR15") (class "Default")
      (node (ref "U1") (pin "21") (pinfunction "A2_21") (pintype "unspecified"))
    )
    (net (code "74") (name "/TR16") (class "Default")
      (node (ref "U1") (pin "22") (pinfunction "A3_22") (pintype "unspecified"))
    )
    (net (code "75") (name "/TR17") (class "Default")
      (node (ref "U1") (pin "23") (pinfunction "A4_23") (pintype "unspecified"))
    )
    (net (code "76") (name "/TR18") (class "Default")
      (node (ref "U1") (pin "24") (pinfunction "A5_24") (pintype "unspecified"))
    )
    (net (code "77") (name "/TR19") (class "Default")
      (node (ref "U2") (pin "5") (pinfunction "D2_5") (pintype "unspecified"))
    )
    (net (code "78") (name "/TR20") (class "Default")
      (node (ref "U2") (pin "6") (pinfunction "D3_6") (pintype "unspecified"))
    )
    (net (code "79") (name "/TR21") (class "Default")
      (node (ref "U2") (pin "7") (pinfunction "D4_7") (pintype "unspecified"))
    )
    (net (code "80") (name "/TR22") (class "Default")
      (node (ref "U2") (pin "8") (pinfunction "D5_8") (pintype "unspecified"))
    )
    (net (code "81") (name "/TR23") (class "Default")
      (node (ref "U2") (pin "9") (pinfunction "D6_9") (pintype "unspecified"))
    )
    (net (code "82") (name "/TR24") (class "Default")
      (node (ref "U2") (pin "10") (pinfunction "D7_10") (pintype "unspecified"))
    )
    (net (code "83") (name "/TR25") (class "Default")
      (node (ref "U2") (pin "11") (pinfunction "D8_11") (pintype "unspecified"))
    )
    (net (code "84") (name "/TR26") (class "Default")
      (node (ref "U2") (pin "12") (pinfunction "D9_12") (pintype "unspecified"))
    )
    (net (code "85") (name "/TR27") (class "Default")
      (node (ref "U2") (pin "13") (pinfunction "D10_13") (pintype "unspecified"))
    )
    (net (code "86") (name "/TR28") (class "Default")
      (node (ref "U2") (pin "14") (pinfunction "D11/MOSI_14") (pintype "unspecified"))
    )
    (net (code "87") (name "/TR29") (class "Default")
      (node (ref "U2") (pin "15") (pinfunction "D12/MISO_15") (pintype "unspecified"))
    )
    (net (code "88") (name "/TR30") (class "Default")
      (node (ref "U2") (pin "16") (pinfunction "D13/SCK_16") (pintype "unspecified"))
    )
    (net (code "89") (name "/TR31") (class "Default")
      (node (ref "U2") (pin "19") (pinfunction "A0_19") (pintype "unspecified"))
    )
    (net (code "90") (name "/TR32") (class "Default")
      (node (ref "U2") (pin "20") (pinfunction "A1_20") (pintype "unspecified"))
    )
    (net (code "91") (name "/TR33") (class "Default")
      (node (ref "U2") (pin "21") (pinfunction "A2_21") (pintype "unspecified"))
    )
    (net (code "92") (name "/TR34") (class "Default")
      (node (ref "U2") (pin "22") (pinfunction "A3_22") (pintype "unspecified"))
    )
    (net (code "93") (name "/TR35") (class "Default")
      (node (ref "U2") (pin "23") (pinfunction "A4_23") (pintype "unspecified"))
    )
    (net (code "94") (name "/TR36") (class "Default")
      (node (ref "U2") (pin "24") (pinfunction "A5_24") (pintype "unspecified"))
    )
    (net (code "95") (name "/TR37") (class "Default")
      (node (ref "U3") (pin "5") (pinfunction "D2_5") (pintype "unspecified"))
    )
    (net (code "96") (name "/TR38") (class "Default")
      (node (ref "U3") (pin "6") (pinfunction "D3_6") (pintype "unspecified"))
    )
    (net (code "97") (name "/TR39") (class "Default")
      (node (ref "U3") (pin "7") (pinfunction "D4_7") (pintype "unspecified"))
    )
    (net (code "98") (name "/TR40") (class "Default")
      (node (ref "U3") (pin "8") (pinfunction "D5_8") (pintype "unspecified"))
    )
    (net (code "99") (name "/TR41") (class "Default")
      (node (ref "U3") (pin "9") (pinfunction "D6_9") (pintype "unspecified"))
    )
    (net (code "100") (name "/TR42") (class "Default")
      (node (ref "U3") (pin "10") (pinfunction "D7_10") (pintype "unspecified"))
    )
    (net (code "101") (name "/TR43") (class "Default")
      (node (ref "U3") (pin "11") (pinfunction "D8_11") (pintype "unspecified"))
    )
    (net (code "102") (name "/TR44") (class "Default")
      (node (ref "U3") (pin "12") (pinfunction "D9_12") (pintype "unspecified"))
    )
    (net (code "103") (name "/TR45") (class "Default")
      (node (ref "U3") (pin "13") (pinfunction "D10_13") (pintype "unspecified"))
    )
    (net (code "104") (name "/TR46") (class "Default")
      (node (ref "U3") (pin "14") (pinfunction "D11/MOSI_14") (pintype "unspecified"))
    )
    (net (code "105") (name "/TR47") (class "Default")
      (node (ref "U3") (pin "15") (pinfunction "D12/MISO_15") (pintype "unspecified"))
    )
    (net (code "106") (name "/TR48") (class "Default")
      (node (ref "U3") (pin "16") (pinfunction "D13/SCK_16") (pintype "unspecified"))
    )
    (net (code "107") (name "/TR49") (class "Default")
      (node (ref "U3") (pin "19") (pinfunction "A0_19") (pintype "unspecified"))
    )
    (net (code "108") (name "/TR50") (class "Default")
      (node (ref "U3") (pin "20") (pinfunction "A1_20") (pintype "unspecified"))
    )
    (net (code "109") (name "/TR51") (class "Default")
      (node (ref "U3") (pin "21") (pinfunction "A2_21") (pintype "unspecified"))
    )
    (net (code "110") (name "/TR52") (class "Default")
      (node (ref "U3") (pin "22") (pinfunction "A3_22") (pintype "unspecified"))
    )
    (net (code "111") (name "/TR53") (class "Default")
      (node (ref "U3") (pin "23") (pinfunction "A4_23") (pintype "unspecified"))
    )
    (net (code "112") (name "/TR54") (class "Default")
      (node (ref "U3") (pin "24") (pinfunction "A5_24") (pintype "unspecified"))
    )
    (net (code "113") (name "GND") (class "Default")
      (node (ref "H1") (pin "1") (pinfunction "1_1") (pintype "input"))
      (node (ref "J1") (pin "1") (pinfunction "1_1") (pintype "input"))
      (node (ref "U1") (pin "29") (pinfunction "GND_29") (pintype "unspecified"))
      (node (ref "U1") (pin "4") (pinfunction "GND_4") (pintype "unspecified"))
      (node (ref "U2") (pin "29") (pinfunction "GND_29") (pintype "unspecified"))
      (node (ref "U2") (pin "4") (pinfunction "GND_4") (pintype "unspecified"))
      (node (ref "U3") (pin "29") (pinfunction "GND_29") (pintype "unspecified"))
      (node (ref "U3") (pin "4") (pinfunction "GND_4") (pintype "unspecified"))
      (node (ref "U4") (pin "4") (pinfunction "GND_4") (pintype "unspecified"))
    )
    (net (code "114") (name "Net-(Q1-B)") (class "Default")
      (node (ref "Q1") (pin "2") (pinfunction "B_2") (pintype "input"))
      (node (ref "R1") (pin "2") (pinfunction "2_2") (pintype "unspecified"))
      (node (ref "R2") (pin "1") (pinfunction "1_1") (pintype "unspecified"))
    )
    (net (code "115") (name "Net-(Q1-C)") (class "Default")
      (node (ref "P1") (pin "2") (pinfunction "2_2") (pintype "unspecified"))
      (node (ref "Q1") (pin "3") (pinfunction "C_3") (pintype "input"))
    )
    (net (code "116") (name "Net-(Q2-B)") (class "Default")
      (node (ref "Q2") (pin "2") (pinfunction "B_2") (pintype "input"))
      (node (ref "R3") (pin "1") (pinfunction "1_1") (pintype "unspecified"))
      (node (ref "R4") (pin "2") (pinfunction "2_2") (pintype "unspecified"))
    )
    (net (code "117") (name "Net-(Q3-B)") (class "Default")
      (node (ref "Q3") (pin "2") (pinfunction "B_2") (pintype "input"))
      (node (ref "R5") (pin "2") (pinfunction "2_2") (pintype "unspecified"))
      (node (ref "R6") (pin "1") (pinfunction "1_1") (pintype "unspecified"))
    )
    (net (code "118") (name "Net-(Q4-B)") (class "Default")
      (node (ref "Q4") (pin "2") (pinfunction "B_2") (pintype "input"))
      (node (ref "R7") (pin "1") (pinfunction "1_1") (pintype "unspecified"))
      (node (ref "R8") (pin "2") (pinfunction "2_2") (pintype "unspecified"))
    )
    (net (code "119") (name "Net-(Q5-B)") (class "Default")
      (node (ref "Q5") (pin "2") (pinfunction "B_2") (pintype "input"))
      (node (ref "R10") (pin "1") (pinfunction "1_1") (pintype "unspecified"))
      (node (ref "R9") (pin "2") (pinfunction "2_2") (pintype "unspecified"))
    )
    (net (code "120") (name "Net-(Q6-B)") (class "Default")
      (node (ref "Q6") (pin "2") (pinfunction "B_2") (pintype "input"))
      (node (ref "R11") (pin "1") (pinfunction "1_1") (pintype "unspecified"))
      (node (ref "R12") (pin "2") (pinfunction "2_2") (pintype "unspecified"))
    )
    (net (code "121") (name "Net-(Q7-B)") (class "Default")
      (node (ref "Q7") (pin "2") (pinfunction "B_2") (pintype "input"))
      (node (ref "R13") (pin "2") (pinfunction "2_2") (pintype "unspecified"))
      (node (ref "R14") (pin "1") (pinfunction "1_1") (pintype "unspecified"))
    )
    (net (code "122") (name "Net-(Q8-B)") (class "Default")
      (node (ref "Q8") (pin "2") (pinfunction "B_2") (pintype "input"))
      (node (ref "R15") (pin "1") (pinfunction "1_1") (pintype "unspecified"))
      (node (ref "R16") (pin "2") (pinfunction "2_2") (pintype "unspecified"))
    )
    (net (code "123") (name "Net-(Q9-B)") (class "Default")
      (node (ref "Q9") (pin "2") (pinfunction "B_2") (pintype "input"))
      (node (ref "R17") (pin "2") (pinfunction "2_2") (pintype "unspecified"))
      (node (ref "R18") (pin "1") (pinfunction "1_1") (pintype "unspecified"))
    )
    (net (code "124") (name "Net-(Q10-B)") (class "Default")
      (node (ref "Q10") (pin "2") (pinfunction "B_2") (pintype "input"))
      (node (ref "R19") (pin "1") (pinfunction "1_1") (pintype "unspecified"))
      (node (ref "R20") (pin "2") (pinfunction "2_2") (pintype "unspecified"))
    )
    (net (code "125") (name "Net-(Q11-B)") (class "Default")
      (node (ref "Q11") (pin "2") (pinfunction "B_2") (pintype "input"))
      (node (ref "R21") (pin "2") (pinfunction "2_2") (pintype "unspecified"))
      (node (ref "R22") (pin "1") (pinfunction "1_1") (pintype "unspecified"))
    )
    (net (code "126") (name "Net-(Q12-B)") (class "Default")
      (node (ref "Q12") (pin "2") (pinfunction "B_2") (pintype "input"))
      (node (ref "R23") (pin "1") (pinfunction "1_1") (pintype "unspecified"))
      (node (ref "R24") (pin "2") (pinfunction "2_2") (pintype "unspecified"))
    )
    (net (code "127") (name "Net-(Q13-B)") (class "Default")
      (node (ref "Q13") (pin "2") (pinfunction "B_2") (pintype "input"))
      (node (ref "R25") (pin "2") (pinfunction "2_2") (pintype "unspecified"))
      (node (ref "R26") (pin "1") (pinfunction "1_1") (pintype "unspecified"))
    )
    (net (code "128") (name "Net-(Q14-B)") (class "Default")
      (node (ref "Q14") (pin "2") (pinfunction "B_2") (pintype "input"))
      (node (ref "R27") (pin "1") (pinfunction "1_1") (pintype "unspecified"))
      (node (ref "R28") (pin "2") (pinfunction "2_2") (pintype "unspecified"))
    )
    (net (code "129") (name "Net-(Q15-B)") (class "Default")
      (node (ref "Q15") (pin "2") (pinfunction "B_2") (pintype "input"))
      (node (ref "R29") (pin "2") (pinfunction "2_2") (pintype "unspecified"))
      (node (ref "R30") (pin "1") (pinfunction "1_1") (pintype "unspecified"))
    )
    (net (code "130") (name "Net-(Q16-B)") (class "Default")
      (node (ref "Q16") (pin "2") (pinfunction "B_2") (pintype "input"))
      (node (ref "R31") (pin "1") (pinfunction "1_1") (pintype "unspecified"))
      (node (ref "R32") (pin "2") (pinfunction "2_2") (pintype "unspecified"))
    )
    (net (code "131") (name "Net-(Q17-B)") (class "Default")
      (node (ref "Q17") (pin "2") (pinfunction "B_2") (pintype "input"))
      (node (ref "R33") (pin "2") (pinfunction "2_2") (pintype "unspecified"))
      (node (ref "R34") (pin "1") (pinfunction "1_1") (pintype "unspecified"))
    )
    (net (code "132") (name "Net-(Q18-B)") (class "Default")
      (node (ref "Q18") (pin "2") (pinfunction "B_2") (pintype "input"))
      (node (ref "R35") (pin "1") (pinfunction "1_1") (pintype "unspecified"))
      (node (ref "R36") (pin "2") (pinfunction "2_2") (pintype "unspecified"))
    )
    (net (code "133") (name "Net-(Q19-B)") (class "Default")
      (node (ref "Q19") (pin "2") (pinfunction "B_2") (pintype "input"))
      (node (ref "R37") (pin "2") (pinfunction "2_2") (pintype "unspecified"))
      (node (ref "R38") (pin "1") (pinfunction "1_1") (pintype "unspecified"))
    )
    (net (code "134") (name "Net-(Q20-B)") (class "Default")
      (node (ref "Q20") (pin "2") (pinfunction "B_2") (pintype "input"))
      (node (ref "R39") (pin "1") (pinfunction "1_1") (pintype "unspecified"))
      (node (ref "R40") (pin "2") (pinfunction "2_2") (pintype "unspecified"))
    )
    (net (code "135") (name "Net-(Q21-B)") (class "Default")
      (node (ref "Q21") (pin "2") (pinfunction "B_2") (pintype "input"))
      (node (ref "R41") (pin "2") (pinfunction "2_2") (pintype "unspecified"))
      (node (ref "R42") (pin "1") (pinfunction "1_1") (pintype "unspecified"))
    )
    (net (code "136") (name "Net-(Q22-B)") (class "Default")
      (node (ref "Q22") (pin "2") (pinfunction "B_2") (pintype "input"))
      (node (ref "R43") (pin "1") (pinfunction "1_1") (pintype "unspecified"))
      (node (ref "R44") (pin "2") (pinfunction "2_2") (pintype "unspecified"))
    )
    (net (code "137") (name "Net-(Q23-B)") (class "Default")
      (node (ref "Q23") (pin "2") (pinfunction "B_2") (pintype "input"))
      (node (ref "R45") (pin "2") (pinfunction "2_2") (pintype "unspecified"))
      (node (ref "R46") (pin "1") (pinfunction "1_1") (pintype "unspecified"))
    )
    (net (code "138") (name "Net-(Q24-B)") (class "Default")
      (node (ref "Q24") (pin "2") (pinfunction "B_2") (pintype "input"))
      (node (ref "R47") (pin "1") (pinfunction "1_1") (pintype "unspecified"))
      (node (ref "R48") (pin "2") (pinfunction "2_2") (pintype "unspecified"))
    )
    (net (code "139") (name "Net-(Q25-B)") (class "Default")
      (node (ref "Q25") (pin "2") (pinfunction "B_2") (pintype "input"))
      (node (ref "R49") (pin "2") (pinfunction "2_2") (pintype "unspecified"))
      (node (ref "R50") (pin "1") (pinfunction "1_1") (pintype "unspecified"))
    )
    (net (code "140") (name "Net-(Q26-B)") (class "Default")
      (node (ref "Q26") (pin "2") (pinfunction "B_2") (pintype "input"))
      (node (ref "R51") (pin "1") (pinfunction "1_1") (pintype "unspecified"))
      (node (ref "R52") (pin "2") (pinfunction "2_2") (pintype "unspecified"))
    )
    (net (code "141") (name "Net-(Q27-B)") (class "Default")
      (node (ref "Q27") (pin "2") (pinfunction "B_2") (pintype "input"))
      (node (ref "R53") (pin "2") (pinfunction "2_2") (pintype "unspecified"))
      (node (ref "R54") (pin "1") (pinfunction "1_1") (pintype "unspecified"))
    )
    (net (code "142") (name "Net-(Q28-B)") (class "Default")
      (node (ref "Q28") (pin "2") (pinfunction "B_2") (pintype "input"))
      (node (ref "R55") (pin "1") (pinfunction "1_1") (pintype "unspecified"))
      (node (ref "R56") (pin "2") (pinfunction "2_2") (pintype "unspecified"))
    )
    (net (code "143") (name "Net-(Q29-B)") (class "Default")
      (node (ref "Q29") (pin "2") (pinfunction "B_2") (pintype "input"))
      (node (ref "R57") (pin "2") (pinfunction "2_2") (pintype "unspecified"))
      (node (ref "R58") (pin "1") (pinfunction "1_1") (pintype "unspecified"))
    )
    (net (code "144") (name "Net-(Q30-B)") (class "Default")
      (node (ref "Q30") (pin "2") (pinfunction "B_2") (pintype "input"))
      (node (ref "R59") (pin "1") (pinfunction "1_1") (pintype "unspecified"))
      (node (ref "R60") (pin "2") (pinfunction "2_2") (pintype "unspecified"))
    )
    (net (code "145") (name "Net-(Q31-B)") (class "Default")
      (node (ref "Q31") (pin "2") (pinfunction "B_2") (pintype "input"))
      (node (ref "R61") (pin "2") (pinfunction "2_2") (pintype "unspecified"))
      (node (ref "R62") (pin "1") (pinfunction "1_1") (pintype "unspecified"))
    )
    (net (code "146") (name "Net-(Q32-B)") (class "Default")
      (node (ref "Q32") (pin "2") (pinfunction "B_2") (pintype "input"))
      (node (ref "R63") (pin "1") (pinfunction "1_1") (pintype "unspecified"))
      (node (ref "R64") (pin "2") (pinfunction "2_2") (pintype "unspecified"))
    )
    (net (code "147") (name "Net-(Q33-B)") (class "Default")
      (node (ref "Q33") (pin "2") (pinfunction "B_2") (pintype "input"))
      (node (ref "R65") (pin "2") (pinfunction "2_2") (pintype "unspecified"))
      (node (ref "R66") (pin "1") (pinfunction "1_1") (pintype "unspecified"))
    )
    (net (code "148") (name "Net-(Q34-B)") (class "Default")
      (node (ref "Q34") (pin "2") (pinfunction "B_2") (pintype "input"))
      (node (ref "R67") (pin "1") (pinfunction "1_1") (pintype "unspecified"))
      (node (ref "R68") (pin "2") (pinfunction "2_2") (pintype "unspecified"))
    )
    (net (code "149") (name "Net-(Q35-B)") (class "Default")
      (node (ref "Q35") (pin "2") (pinfunction "B_2") (pintype "input"))
      (node (ref "R69") (pin "2") (pinfunction "2_2") (pintype "unspecified"))
      (node (ref "R70") (pin "1") (pinfunction "1_1") (pintype "unspecified"))
    )
    (net (code "150") (name "Net-(Q36-B)") (class "Default")
      (node (ref "Q36") (pin "2") (pinfunction "B_2") (pintype "input"))
      (node (ref "R71") (pin "1") (pinfunction "1_1") (pintype "unspecified"))
      (node (ref "R72") (pin "2") (pinfunction "2_2") (pintype "unspecified"))
    )
    (net (code "151") (name "Net-(Q37-B)") (class "Default")
      (node (ref "Q37") (pin "2") (pinfunction "B_2") (pintype "input"))
      (node (ref "R73") (pin "2") (pinfunction "2_2") (pintype "unspecified"))
      (node (ref "R74") (pin "1") (pinfunction "1_1") (pintype "unspecified"))
    )
    (net (code "152") (name "Net-(Q38-B)") (class "Default")
      (node (ref "Q38") (pin "2") (pinfunction "B_2") (pintype "input"))
      (node (ref "R75") (pin "1") (pinfunction "1_1") (pintype "unspecified"))
      (node (ref "R76") (pin "2") (pinfunction "2_2") (pintype "unspecified"))
    )
    (net (code "153") (name "Net-(Q39-B)") (class "Default")
      (node (ref "Q39") (pin "2") (pinfunction "B_2") (pintype "input"))
      (node (ref "R77") (pin "2") (pinfunction "2_2") (pintype "unspecified"))
      (node (ref "R78") (pin "1") (pinfunction "1_1") (pintype "unspecified"))
    )
    (net (code "154") (name "Net-(Q40-B)") (class "Default")
      (node (ref "Q40") (pin "2") (pinfunction "B_2") (pintype "input"))
      (node (ref "R79") (pin "1") (pinfunction "1_1") (pintype "unspecified"))
      (node (ref "R80") (pin "2") (pinfunction "2_2") (pintype "unspecified"))
    )
    (net (code "155") (name "Net-(Q41-B)") (class "Default")
      (node (ref "Q41") (pin "2") (pinfunction "B_2") (pintype "input"))
      (node (ref "R81") (pin "2") (pinfunction "2_2") (pintype "unspecified"))
      (node (ref "R82") (pin "1") (pinfunction "1_1") (pintype "unspecified"))
    )
    (net (code "156") (name "Net-(Q42-B)") (class "Default")
      (node (ref "Q42") (pin "2") (pinfunction "B_2") (pintype "input"))
      (node (ref "R83") (pin "1") (pinfunction "1_1") (pintype "unspecified"))
      (node (ref "R84") (pin "2") (pinfunction "2_2") (pintype "unspecified"))
    )
    (net (code "157") (name "Net-(Q43-B)") (class "Default")
      (node (ref "Q43") (pin "2") (pinfunction "B_2") (pintype "input"))
      (node (ref "R85") (pin "2") (pinfunction "2_2") (pintype "unspecified"))
      (node (ref "R86") (pin "1") (pinfunction "1_1") (pintype "unspecified"))
    )
    (net (code "158") (name "Net-(Q44-B)") (class "Default")
      (node (ref "Q44") (pin "2") (pinfunction "B_2") (pintype "input"))
      (node (ref "R87") (pin "1") (pinfunction "1_1") (pintype "unspecified"))
      (node (ref "R88") (pin "2") (pinfunction "2_2") (pintype "unspecified"))
    )
    (net (code "159") (name "Net-(Q45-B)") (class "Default")
      (node (ref "Q45") (pin "2") (pinfunction "B_2") (pintype "input"))
      (node (ref "R89") (pin "2") (pinfunction "2_2") (pintype "unspecified"))
      (node (ref "R90") (pin "1") (pinfunction "1_1") (pintype "unspecified"))
    )
    (net (code "160") (name "Net-(Q46-B)") (class "Default")
      (node (ref "Q46") (pin "2") (pinfunction "B_2") (pintype "input"))
      (node (ref "R91") (pin "1") (pinfunction "1_1") (pintype "unspecified"))
      (node (ref "R92") (pin "2") (pinfunction "2_2") (pintype "unspecified"))
    )
    (net (code "161") (name "Net-(Q47-B)") (class "Default")
      (node (ref "Q47") (pin "2") (pinfunction "B_2") (pintype "input"))
      (node (ref "R93") (pin "2") (pinfunction "2_2") (pintype "unspecified"))
      (node (ref "R94") (pin "1") (pinfunction "1_1") (pintype "unspecified"))
    )
    (net (code "162") (name "Net-(Q48-B)") (class "Default")
      (node (ref "Q48") (pin "2") (pinfunction "B_2") (pintype "input"))
      (node (ref "R95") (pin "1") (pinfunction "1_1") (pintype "unspecified"))
      (node (ref "R96") (pin "2") (pinfunction "2_2") (pintype "unspecified"))
    )
    (net (code "163") (name "Net-(Q49-B)") (class "Default")
      (node (ref "Q49") (pin "2") (pinfunction "B_2") (pintype "input"))
      (node (ref "R97") (pin "2") (pinfunction "2_2") (pintype "unspecified"))
      (node (ref "R98") (pin "1") (pinfunction "1_1") (pintype "unspecified"))
    )
    (net (code "164") (name "Net-(Q50-B)") (class "Default")
      (node (ref "Q50") (pin "2") (pinfunction "B_2") (pintype "input"))
      (node (ref "R100") (pin "2") (pinfunction "2_2") (pintype "unspecified"))
      (node (ref "R99") (pin "1") (pinfunction "1_1") (pintype "unspecified"))
    )
    (net (code "165") (name "Net-(Q51-B)") (class "Default")
      (node (ref "Q51") (pin "2") (pinfunction "B_2") (pintype "input"))
      (node (ref "R101") (pin "2") (pinfunction "2_2") (pintype "unspecified"))
      (node (ref "R102") (pin "1") (pinfunction "1_1") (pintype "unspecified"))
    )
    (net (code "166") (name "Net-(Q57-B)") (class "Default")
      (node (ref "Q57") (pin "2") (pinfunction "B_2") (pintype "input"))
      (node (ref "R113") (pin "2") (pinfunction "2_2") (pintype "unspecified"))
      (node (ref "R114") (pin "1") (pinfunction "1_1") (pintype "unspecified"))
    )
    (net (code "167") (name "Net-(Q59-B)") (class "Default")
      (node (ref "Q59") (pin "2") (pinfunction "B_2") (pintype "input"))
      (node (ref "R117") (pin "2") (pinfunction "2_2") (pintype "unspecified"))
      (node (ref "R118") (pin "1") (pinfunction "1_1") (pintype "unspecified"))
    )
    (net (code "168") (name "Net-(Q60-B)") (class "Default")
      (node (ref "Q60") (pin "2") (pinfunction "B_2") (pintype "input"))
      (node (ref "R119") (pin "1") (pinfunction "1_1") (pintype "unspecified"))
      (node (ref "R120") (pin "2") (pinfunction "2_2") (pintype "unspecified"))
    )
    (net (code "169") (name "Net-(Q61-B)") (class "Default")
      (node (ref "Q61") (pin "2") (pinfunction "B_2") (pintype "input"))
      (node (ref "R121") (pin "2") (pinfunction "2_2") (pintype "unspecified"))
      (node (ref "R122") (pin "1") (pinfunction "1_1") (pintype "unspecified"))
    )
    (net (code "170") (name "Net-(U4-PB0(MOSI))") (class "Default")
      (node (ref "R1") (pin "1") (pinfunction "1_1") (pintype "unspecified"))
      (node (ref "U4") (pin "5") (pinfunction "PB0(MOSI)_5") (pintype "unspecified"))
    )
    (net (code "171") (name "Net-(U4-PB1(MISO))") (class "Default")
      (node (ref "H1") (pin "3") (pinfunction "3_3") (pintype "input"))
      (node (ref "U4") (pin "6") (pinfunction "PB1(MISO)_6") (pintype "unspecified"))
    )
    (net (code "172") (name "netPort1") (class "Default")
      (node (ref "U1") (pin "1") (pinfunction "D1/TX_1") (pintype "unspecified"))
      (node (ref "U2") (pin "1") (pinfunction "D1/TX_1") (pintype "unspecified"))
      (node (ref "U3") (pin "1") (pinfunction "D1/TX_1") (pintype "unspecified"))
    )
    (net (code "173") (name "netPort2") (class "Default")
      (node (ref "U1") (pin "2") (pinfunction "D0/RX_2") (pintype "unspecified"))
      (node (ref "U2") (pin "2") (pinfunction "D0/RX_2") (pintype "unspecified"))
      (node (ref "U3") (pin "2") (pinfunction "D0/RX_2") (pintype "unspecified"))
    )
    (net (code "174") (name "unconnected-(Q32-C-Pad3)") (class "Default")
      (node (ref "Q32") (pin "3") (pinfunction "C_3") (pintype "input"))
    )
    (net (code "175") (name "unconnected-(R4-Pad1)") (class "Default")
      (node (ref "R4") (pin "1") (pinfunction "1_1") (pintype "unspecified"))
    )
    (net (code "176") (name "unconnected-(R5-Pad1)") (class "Default")
      (node (ref "R5") (pin "1") (pinfunction "1_1") (pintype "unspecified"))
    )
    (net (code "177") (name "unconnected-(R8-Pad1)") (class "Default")
      (node (ref "R8") (pin "1") (pinfunction "1_1") (pintype "unspecified"))
    )
    (net (code "178") (name "unconnected-(R9-Pad1)") (class "Default")
      (node (ref "R9") (pin "1") (pinfunction "1_1") (pintype "unspecified"))
    )
    (net (code "179") (name "unconnected-(R12-Pad1)") (class "Default")
      (node (ref "R12") (pin "1") (pinfunction "1_1") (pintype "unspecified"))
    )
    (net (code "180") (name "unconnected-(R13-Pad1)") (class "Default")
      (node (ref "R13") (pin "1") (pinfunction "1_1") (pintype "unspecified"))
    )
    (net (code "181") (name "unconnected-(R16-Pad1)") (class "Default")
      (node (ref "R16") (pin "1") (pinfunction "1_1") (pintype "unspecified"))
    )
    (net (code "182") (name "unconnected-(R17-Pad1)") (class "Default")
      (node (ref "R17") (pin "1") (pinfunction "1_1") (pintype "unspecified"))
    )
    (net (code "183") (name "unconnected-(R20-Pad1)") (class "Default")
      (node (ref "R20") (pin "1") (pinfunction "1_1") (pintype "unspecified"))
    )
    (net (code "184") (name "unconnected-(R21-Pad1)") (class "Default")
      (node (ref "R21") (pin "1") (pinfunction "1_1") (pintype "unspecified"))
    )
    (net (code "185") (name "unconnected-(R24-Pad1)") (class "Default")
      (node (ref "R24") (pin "1") (pinfunction "1_1") (pintype "unspecified"))
    )
    (net (code "186") (name "unconnected-(R25-Pad1)") (class "Default")
      (node (ref "R25") (pin "1") (pinfunction "1_1") (pintype "unspecified"))
    )
    (net (code "187") (name "unconnected-(R28-Pad1)") (class "Default")
      (node (ref "R28") (pin "1") (pinfunction "1_1") (pintype "unspecified"))
    )
    (net (code "188") (name "unconnected-(R29-Pad1)") (class "Default")
      (node (ref "R29") (pin "1") (pinfunction "1_1") (pintype "unspecified"))
    )
    (net (code "189") (name "unconnected-(R32-Pad1)") (class "Default")
      (node (ref "R32") (pin "1") (pinfunction "1_1") (pintype "unspecified"))
    )
    (net (code "190") (name "unconnected-(R33-Pad1)") (class "Default")
      (node (ref "R33") (pin "1") (pinfunction "1_1") (pintype "unspecified"))
    )
    (net (code "191") (name "unconnected-(R36-Pad1)") (class "Default")
      (node (ref "R36") (pin "1") (pinfunction "1_1") (pintype "unspecified"))
    )
    (net (code "192") (name "unconnected-(R37-Pad1)") (class "Default")
      (node (ref "R37") (pin "1") (pinfunction "1_1") (pintype "unspecified"))
    )
    (net (code "193") (name "unconnected-(R40-Pad1)") (class "Default")
      (node (ref "R40") (pin "1") (pinfunction "1_1") (pintype "unspecified"))
    )
    (net (code "194") (name "unconnected-(R41-Pad1)") (class "Default")
      (node (ref "R41") (pin "1") (pinfunction "1_1") (pintype "unspecified"))
    )
    (net (code "195") (name "unconnected-(R44-Pad1)") (class "Default")
      (node (ref "R44") (pin "1") (pinfunction "1_1") (pintype "unspecified"))
    )
    (net (code "196") (name "unconnected-(R45-Pad1)") (class "Default")
      (node (ref "R45") (pin "1") (pinfunction "1_1") (pintype "unspecified"))
    )
    (net (code "197") (name "unconnected-(R48-Pad1)") (class "Default")
      (node (ref "R48") (pin "1") (pinfunction "1_1") (pintype "unspecified"))
    )
    (net (code "198") (name "unconnected-(R49-Pad1)") (class "Default")
      (node (ref "R49") (pin "1") (pinfunction "1_1") (pintype "unspecified"))
    )
    (net (code "199") (name "unconnected-(R52-Pad1)") (class "Default")
      (node (ref "R52") (pin "1") (pinfunction "1_1") (pintype "unspecified"))
    )
    (net (code "200") (name "unconnected-(R53-Pad1)") (class "Default")
      (node (ref "R53") (pin "1") (pinfunction "1_1") (pintype "unspecified"))
    )
    (net (code "201") (name "unconnected-(R56-Pad1)") (class "Default")
      (node (ref "R56") (pin "1") (pinfunction "1_1") (pintype "unspecified"))
    )
    (net (code "202") (name "unconnected-(R57-Pad1)") (class "Default")
      (node (ref "R57") (pin "1") (pinfunction "1_1") (pintype "unspecified"))
    )
    (net (code "203") (name "unconnected-(R60-Pad1)") (class "Default")
      (node (ref "R60") (pin "1") (pinfunction "1_1") (pintype "unspecified"))
    )
    (net (code "204") (name "unconnected-(R61-Pad1)") (class "Default")
      (node (ref "R61") (pin "1") (pinfunction "1_1") (pintype "unspecified"))
    )
    (net (code "205") (name "unconnected-(R64-Pad1)") (class "Default")
      (node (ref "R64") (pin "1") (pinfunction "1_1") (pintype "unspecified"))
    )
    (net (code "206") (name "unconnected-(R65-Pad1)") (class "Default")
      (node (ref "R65") (pin "1") (pinfunction "1_1") (pintype "unspecified"))
    )
    (net (code "207") (name "unconnected-(R68-Pad1)") (class "Default")
      (node (ref "R68") (pin "1") (pinfunction "1_1") (pintype "unspecified"))
    )
    (net (code "208") (name "unconnected-(R69-Pad1)") (class "Default")
      (node (ref "R69") (pin "1") (pinfunction "1_1") (pintype "unspecified"))
    )
    (net (code "209") (name "unconnected-(R72-Pad1)") (class "Default")
      (node (ref "R72") (pin "1") (pinfunction "1_1") (pintype "unspecified"))
    )
    (net (code "210") (name "unconnected-(R73-Pad1)") (class "Default")
      (node (ref "R73") (pin "1") (pinfunction "1_1") (pintype "unspecified"))
    )
    (net (code "211") (name "unconnected-(R76-Pad1)") (class "Default")
      (node (ref "R76") (pin "1") (pinfunction "1_1") (pintype "unspecified"))
    )
    (net (code "212") (name "unconnected-(R77-Pad1)") (class "Default")
      (node (ref "R77") (pin "1") (pinfunction "1_1") (pintype "unspecified"))
    )
    (net (code "213") (name "unconnected-(R80-Pad1)") (class "Default")
      (node (ref "R80") (pin "1") (pinfunction "1_1") (pintype "unspecified"))
    )
    (net (code "214") (name "unconnected-(R81-Pad1)") (class "Default")
      (node (ref "R81") (pin "1") (pinfunction "1_1") (pintype "unspecified"))
    )
    (net (code "215") (name "unconnected-(R84-Pad1)") (class "Default")
      (node (ref "R84") (pin "1") (pinfunction "1_1") (pintype "unspecified"))
    )
    (net (code "216") (name "unconnected-(R85-Pad1)") (class "Default")
      (node (ref "R85") (pin "1") (pinfunction "1_1") (pintype "unspecified"))
    )
    (net (code "217") (name "unconnected-(R88-Pad1)") (class "Default")
      (node (ref "R88") (pin "1") (pinfunction "1_1") (pintype "unspecified"))
    )
    (net (code "218") (name "unconnected-(R89-Pad1)") (class "Default")
      (node (ref "R89") (pin "1") (pinfunction "1_1") (pintype "unspecified"))
    )
    (net (code "219") (name "unconnected-(R92-Pad1)") (class "Default")
      (node (ref "R92") (pin "1") (pinfunction "1_1") (pintype "unspecified"))
    )
    (net (code "220") (name "unconnected-(R93-Pad1)") (class "Default")
      (node (ref "R93") (pin "1") (pinfunction "1_1") (pintype "unspecified"))
    )
    (net (code "221") (name "unconnected-(R96-Pad1)") (class "Default")
      (node (ref "R96") (pin "1") (pinfunction "1_1") (pintype "unspecified"))
    )
    (net (code "222") (name "unconnected-(R97-Pad1)") (class "Default")
      (node (ref "R97") (pin "1") (pinfunction "1_1") (pintype "unspecified"))
    )
    (net (code "223") (name "unconnected-(R100-Pad1)") (class "Default")
      (node (ref "R100") (pin "1") (pinfunction "1_1") (pintype "unspecified"))
    )
    (net (code "224") (name "unconnected-(R101-Pad1)") (class "Default")
      (node (ref "R101") (pin "1") (pinfunction "1_1") (pintype "unspecified"))
    )
    (net (code "225") (name "unconnected-(R113-Pad1)") (class "Default")
      (node (ref "R113") (pin "1") (pinfunction "1_1") (pintype "unspecified"))
    )
    (net (code "226") (name "unconnected-(R117-Pad1)") (class "Default")
      (node (ref "R117") (pin "1") (pinfunction "1_1") (pintype "unspecified"))
    )
    (net (code "227") (name "unconnected-(R120-Pad1)") (class "Default")
      (node (ref "R120") (pin "1") (pinfunction "1_1") (pintype "unspecified"))
    )
    (net (code "228") (name "unconnected-(R121-Pad1)") (class "Default")
      (node (ref "R121") (pin "1") (pinfunction "1_1") (pintype "unspecified"))
    )
    (net (code "229") (name "unconnected-(U1-3V3-Pad17)") (class "Default")
      (node (ref "U1") (pin "17") (pinfunction "3V3_17") (pintype "unspecified"))
    )
    (net (code "230") (name "unconnected-(U1-A6-Pad25)") (class "Default")
      (node (ref "U1") (pin "25") (pinfunction "A6_25") (pintype "unspecified"))
    )
    (net (code "231") (name "unconnected-(U1-A7-Pad26)") (class "Default")
      (node (ref "U1") (pin "26") (pinfunction "A7_26") (pintype "unspecified"))
    )
    (net (code "232") (name "unconnected-(U1-AREF-Pad18)") (class "Default")
      (node (ref "U1") (pin "18") (pinfunction "AREF_18") (pintype "unspecified"))
    )
    (net (code "233") (name "unconnected-(U1-RESET-Pad3)") (class "Default")
      (node (ref "U1") (pin "3") (pinfunction "RESET_3") (pintype "unspecified"))
    )
    (net (code "234") (name "unconnected-(U1-RESET-Pad28)") (class "Default")
      (node (ref "U1") (pin "28") (pinfunction "RESET_28") (pintype "unspecified"))
    )
    (net (code "235") (name "unconnected-(U2-3V3-Pad17)") (class "Default")
      (node (ref "U2") (pin "17") (pinfunction "3V3_17") (pintype "unspecified"))
    )
    (net (code "236") (name "unconnected-(U2-A6-Pad25)") (class "Default")
      (node (ref "U2") (pin "25") (pinfunction "A6_25") (pintype "unspecified"))
    )
    (net (code "237") (name "unconnected-(U2-A7-Pad26)") (class "Default")
      (node (ref "U2") (pin "26") (pinfunction "A7_26") (pintype "unspecified"))
    )
    (net (code "238") (name "unconnected-(U2-AREF-Pad18)") (class "Default")
      (node (ref "U2") (pin "18") (pinfunction "AREF_18") (pintype "unspecified"))
    )
    (net (code "239") (name "unconnected-(U2-RESET-Pad3)") (class "Default")
      (node (ref "U2") (pin "3") (pinfunction "RESET_3") (pintype "unspecified"))
    )
    (net (code "240") (name "unconnected-(U2-RESET-Pad28)") (class "Default")
      (node (ref "U2") (pin "28") (pinfunction "RESET_28") (pintype "unspecified"))
    )
    (net (code "241") (name "unconnected-(U3-3V3-Pad17)") (class "Default")
      (node (ref "U3") (pin "17") (pinfunction "3V3_17") (pintype "unspecified"))
    )
    (net (code "242") (name "unconnected-(U3-A6-Pad25)") (class "Default")
      (node (ref "U3") (pin "25") (pinfunction "A6_25") (pintype "unspecified"))
    )
    (net (code "243") (name "unconnected-(U3-A7-Pad26)") (class "Default")
      (node (ref "U3") (pin "26") (pinfunction "A7_26") (pintype "unspecified"))
    )
    (net (code "244") (name "unconnected-(U3-AREF-Pad18)") (class "Default")
      (node (ref "U3") (pin "18") (pinfunction "AREF_18") (pintype "unspecified"))
    )
    (net (code "245") (name "unconnected-(U3-RESET-Pad3)") (class "Default")
      (node (ref "U3") (pin "3") (pinfunction "RESET_3") (pintype "unspecified"))
    )
    (net (code "246") (name "unconnected-(U3-RESET-Pad28)") (class "Default")
      (node (ref "U3") (pin "28") (pinfunction "RESET_28") (pintype "unspecified"))
    )
    (net (code "247") (name "unconnected-(U4-PB2(SCKADC1)-Pad7)") (class "Default")
      (node (ref "U4") (pin "7") (pinfunction "PB2(SCKADC1)_7") (pintype "unspecified"))
    )
    (net (code "248") (name "unconnected-(U4-PB3(ADC3)-Pad2)") (class "Default")
      (node (ref "U4") (pin "2") (pinfunction "PB3(ADC3)_2") (pintype "unspecified"))
    )
    (net (code "249") (name "unconnected-(U4-PB4(ADC2)-Pad3)") (class "Default")
      (node (ref "U4") (pin "3") (pinfunction "PB4(ADC2)_3") (pintype "unspecified"))
    )
    (net (code "250") (name "unconnected-(U4-PB5(NRES)-Pad1)") (class "Default")
      (node (ref "U4") (pin "1") (pinfunction "PB5(NRES)_1") (pintype "unspecified"))
    )
  )
)
